# schematic.net
KiCad netlist of a schematic drawn in Altium Designer
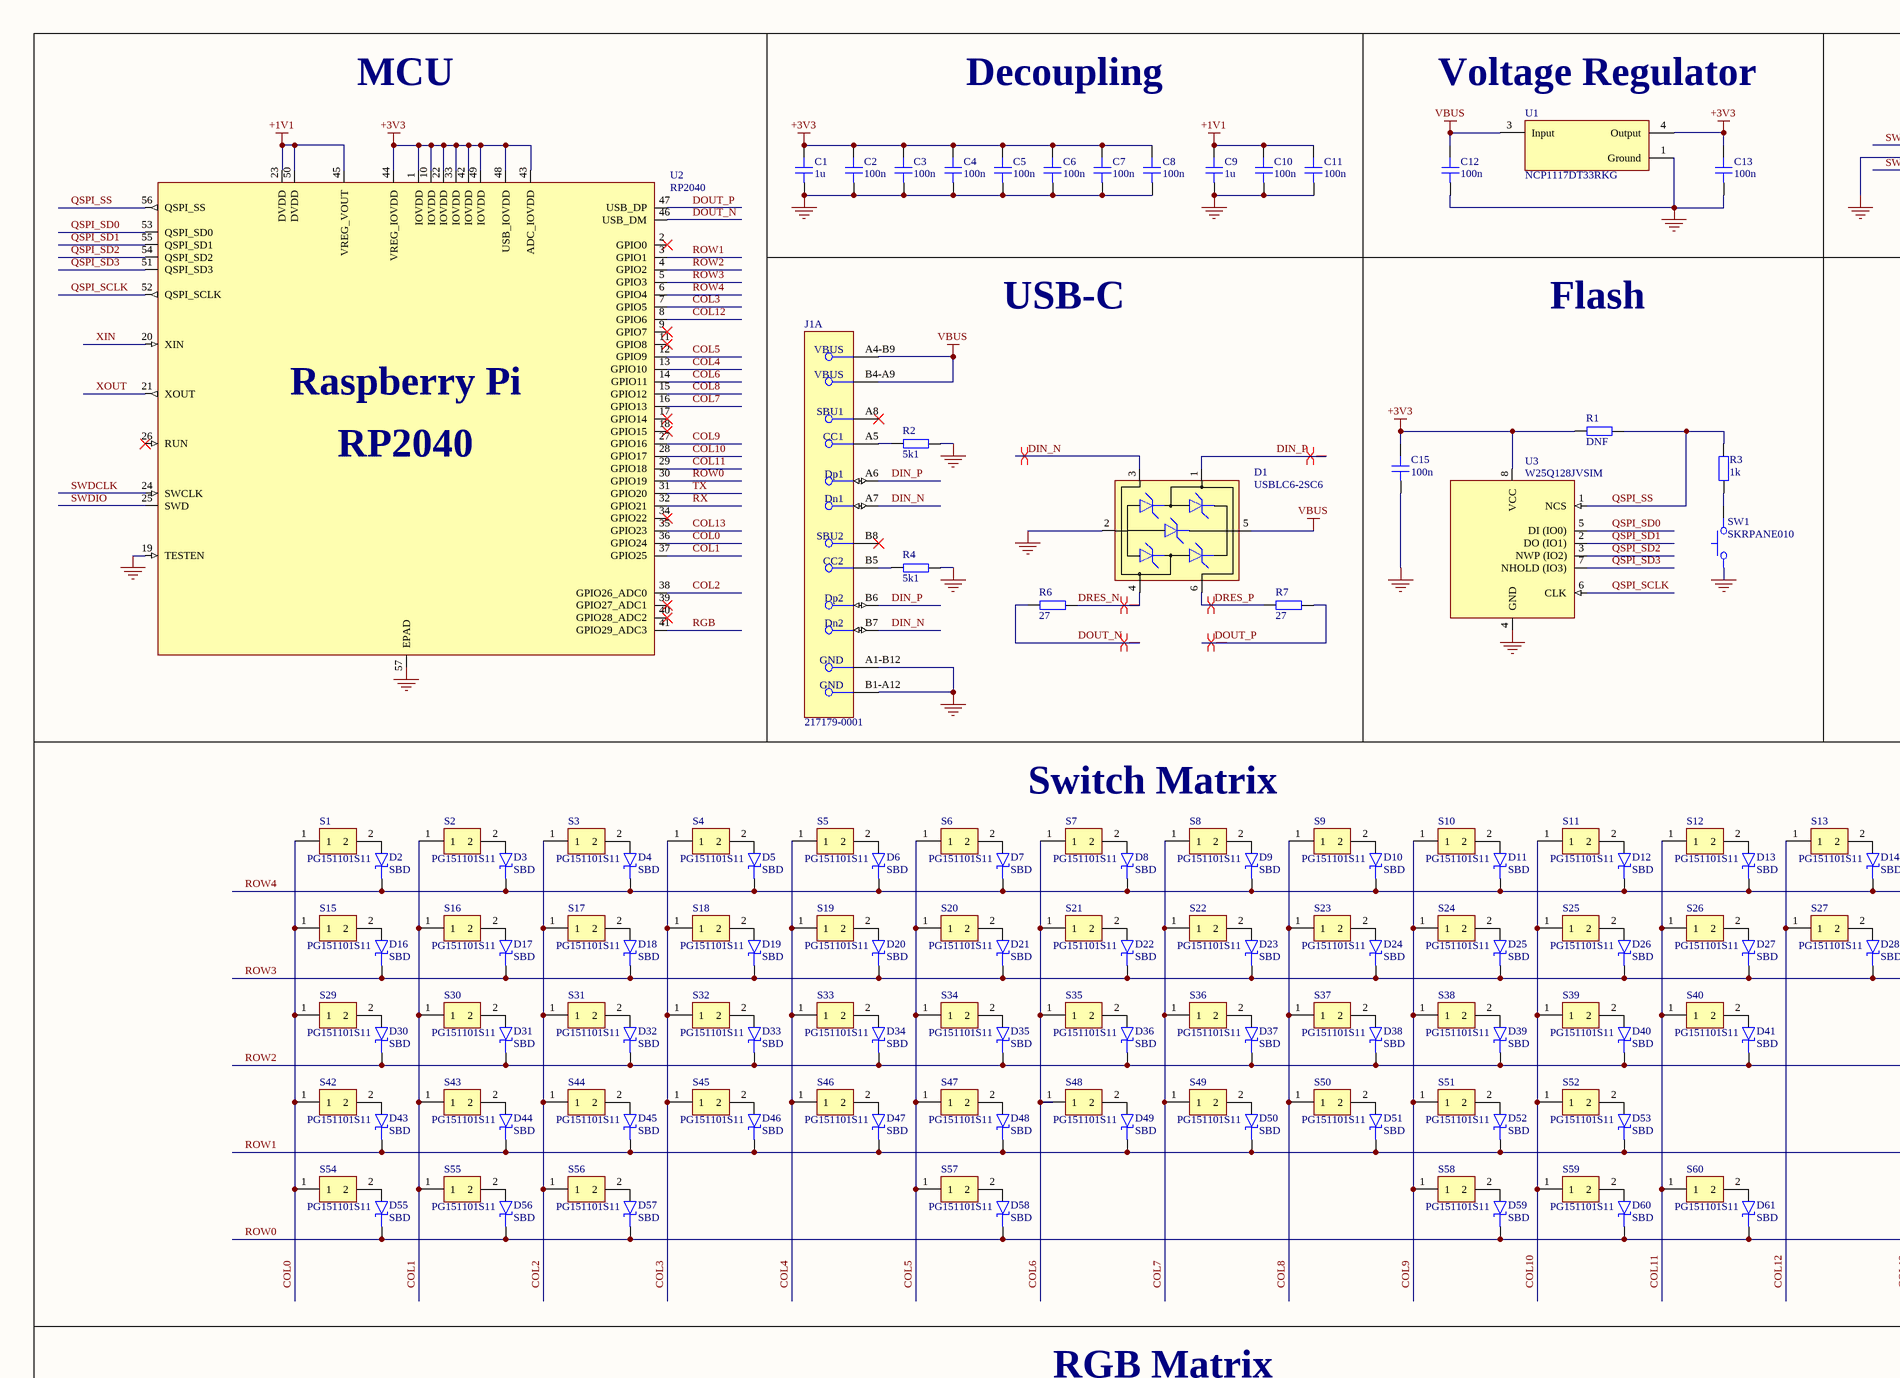
[diagram p0: schematic.SchDoc, top left]
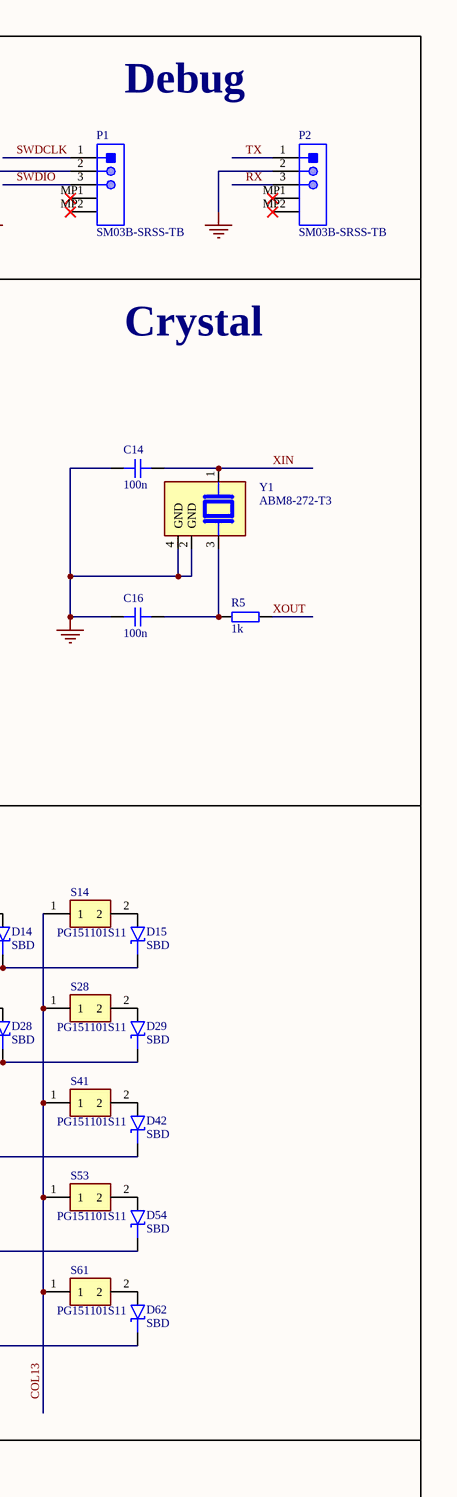
[diagram p1: schematic.SchDoc, top right]
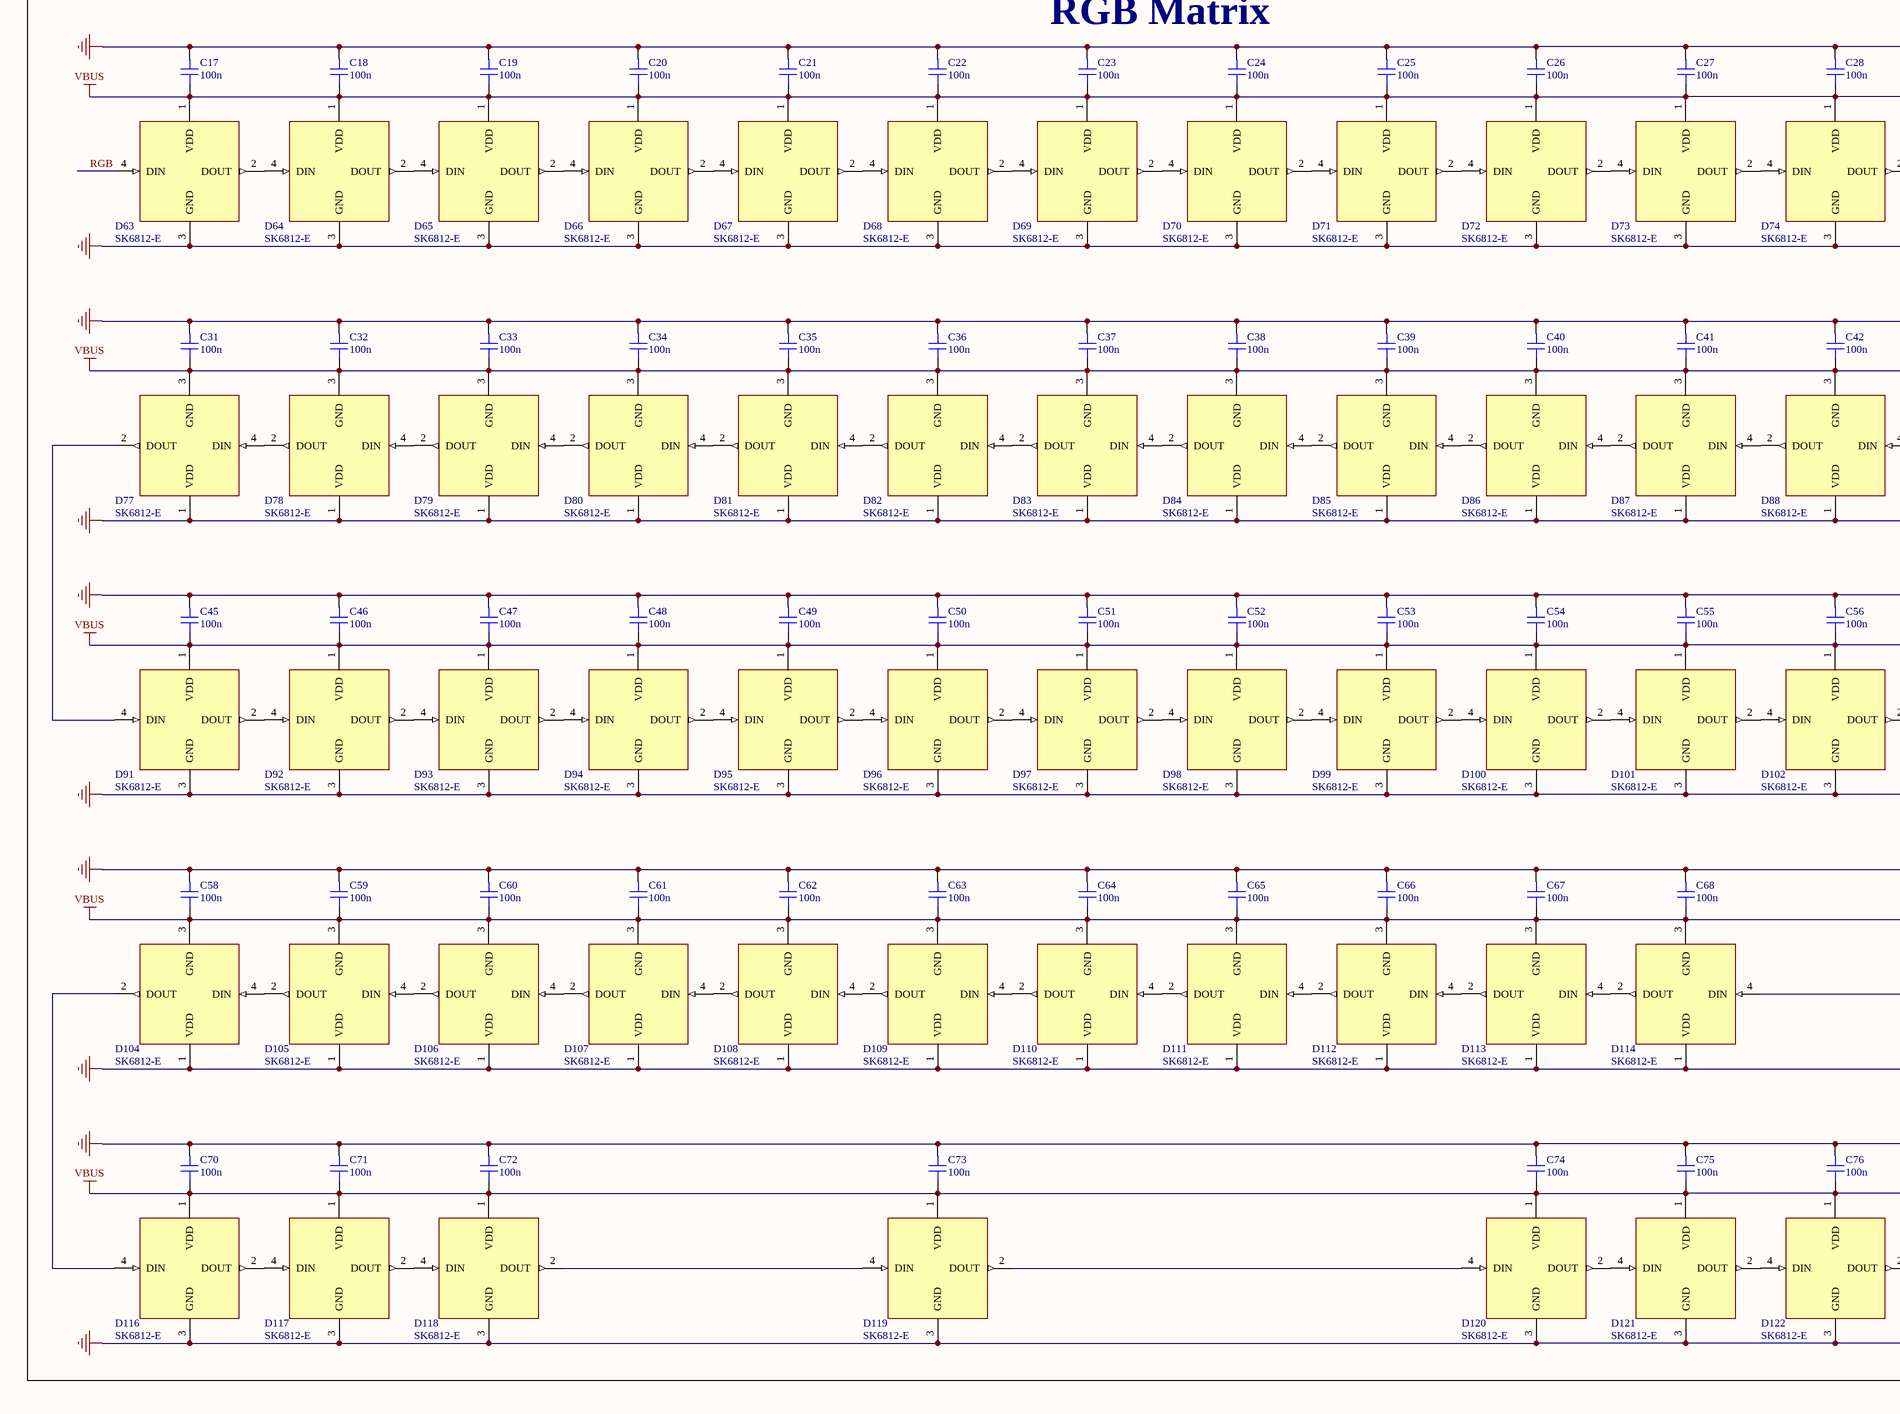
[diagram p2: schematic.SchDoc, bottom left]
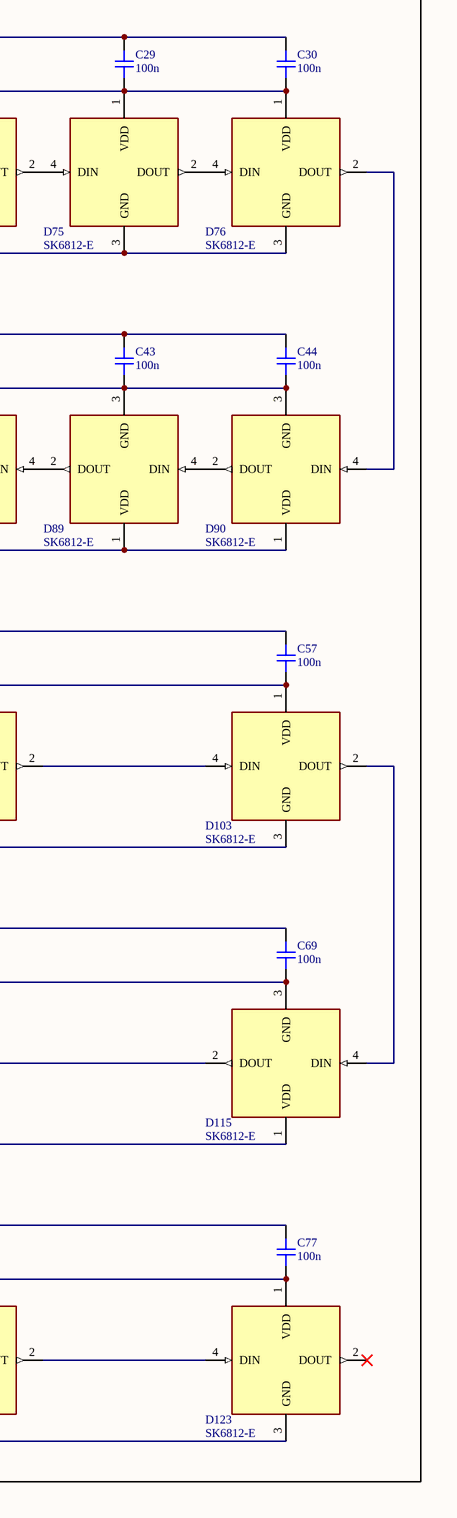
[diagram p3: schematic.SchDoc, bottom right]

(export (version "E")
  (design (tool "Eeschema 10.0.6"))
  (components
    (comp (ref "C1")
      (value "1u")
      (footprint "CAP_0402")
      (description "Capacitor SMD 0402")
      (libsource (lib "Schematic-Lib-PhilsLab") (part "CAP_0402"))
    )
    (comp (ref "C2")
      (value "100n")
      (footprint "CAP_0402")
      (description "Capacitor SMD 0402")
      (libsource (lib "Schematic-Lib-PhilsLab") (part "CAP_0402"))
    )
    (comp (ref "C3")
      (value "100n")
      (footprint "CAP_0402")
      (description "Capacitor SMD 0402")
      (libsource (lib "Schematic-Lib-PhilsLab") (part "CAP_0402"))
    )
    (comp (ref "C4")
      (value "100n")
      (footprint "CAP_0402")
      (description "Capacitor SMD 0402")
      (libsource (lib "Schematic-Lib-PhilsLab") (part "CAP_0402"))
    )
    (comp (ref "C5")
      (value "100n")
      (footprint "CAP_0402")
      (description "Capacitor SMD 0402")
      (libsource (lib "Schematic-Lib-PhilsLab") (part "CAP_0402"))
    )
    (comp (ref "C6")
      (value "100n")
      (footprint "CAP_0402")
      (description "Capacitor SMD 0402")
      (libsource (lib "Schematic-Lib-PhilsLab") (part "CAP_0402"))
    )
    (comp (ref "C7")
      (value "100n")
      (footprint "CAP_0402")
      (description "Capacitor SMD 0402")
      (libsource (lib "Schematic-Lib-PhilsLab") (part "CAP_0402"))
    )
    (comp (ref "C8")
      (value "100n")
      (footprint "CAP_0402")
      (description "Capacitor SMD 0402")
      (libsource (lib "Schematic-Lib-PhilsLab") (part "CAP_0402"))
    )
    (comp (ref "C9")
      (value "1u")
      (footprint "CAP_0402")
      (description "Capacitor SMD 0402")
      (libsource (lib "Schematic-Lib-PhilsLab") (part "CAP_0402"))
    )
    (comp (ref "C10")
      (value "100n")
      (footprint "CAP_0402")
      (description "Capacitor SMD 0402")
      (libsource (lib "Schematic-Lib-PhilsLab") (part "CAP_0402"))
    )
    (comp (ref "C11")
      (value "100n")
      (footprint "CAP_0402")
      (description "Capacitor SMD 0402")
      (libsource (lib "Schematic-Lib-PhilsLab") (part "CAP_0402"))
    )
    (comp (ref "C12")
      (value "100n")
      (footprint "CAP_0402")
      (description "Capacitor SMD 0402")
      (libsource (lib "Schematic-Lib-PhilsLab") (part "CAP_0402"))
    )
    (comp (ref "C13")
      (value "100n")
      (footprint "CAP_0402")
      (description "Capacitor SMD 0402")
      (libsource (lib "Schematic-Lib-PhilsLab") (part "CAP_0402"))
    )
    (comp (ref "C14")
      (value "100n")
      (footprint "CAP_0402")
      (description "Capacitor SMD 0402")
      (libsource (lib "Schematic-Lib-PhilsLab") (part "CAP_0402"))
    )
    (comp (ref "C15")
      (value "100n")
      (footprint "CAP_0402")
      (description "Capacitor SMD 0402")
      (libsource (lib "Schematic-Lib-PhilsLab") (part "CAP_0402"))
    )
    (comp (ref "C16")
      (value "100n")
      (footprint "CAP_0402")
      (description "Capacitor SMD 0402")
      (libsource (lib "Schematic-Lib-PhilsLab") (part "CAP_0402"))
    )
    (comp (ref "C17")
      (value "100n")
      (footprint "CAP_1206")
      (description "Capacitor SMD 1206")
      (libsource (lib "Schematic-Lib-PhilsLab") (part "CAP_1206"))
    )
    (comp (ref "C18")
      (value "100n")
      (footprint "CAP_1206")
      (description "Capacitor SMD 1206")
      (libsource (lib "Schematic-Lib-PhilsLab") (part "CAP_1206"))
    )
    (comp (ref "C19")
      (value "100n")
      (footprint "CAP_1206")
      (description "Capacitor SMD 1206")
      (libsource (lib "Schematic-Lib-PhilsLab") (part "CAP_1206"))
    )
    (comp (ref "C20")
      (value "100n")
      (footprint "CAP_1206")
      (description "Capacitor SMD 1206")
      (libsource (lib "Schematic-Lib-PhilsLab") (part "CAP_1206"))
    )
    (comp (ref "C21")
      (value "100n")
      (footprint "CAP_1206")
      (description "Capacitor SMD 1206")
      (libsource (lib "Schematic-Lib-PhilsLab") (part "CAP_1206"))
    )
    (comp (ref "C22")
      (value "100n")
      (footprint "CAP_1206")
      (description "Capacitor SMD 1206")
      (libsource (lib "Schematic-Lib-PhilsLab") (part "CAP_1206"))
    )
    (comp (ref "C23")
      (value "100n")
      (footprint "CAP_1206")
      (description "Capacitor SMD 1206")
      (libsource (lib "Schematic-Lib-PhilsLab") (part "CAP_1206"))
    )
    (comp (ref "C24")
      (value "100n")
      (footprint "CAP_1206")
      (description "Capacitor SMD 1206")
      (libsource (lib "Schematic-Lib-PhilsLab") (part "CAP_1206"))
    )
    (comp (ref "C25")
      (value "100n")
      (footprint "CAP_1206")
      (description "Capacitor SMD 1206")
      (libsource (lib "Schematic-Lib-PhilsLab") (part "CAP_1206"))
    )
    (comp (ref "C26")
      (value "100n")
      (footprint "CAP_1206")
      (description "Capacitor SMD 1206")
      (libsource (lib "Schematic-Lib-PhilsLab") (part "CAP_1206"))
    )
    (comp (ref "C27")
      (value "100n")
      (footprint "CAP_1206")
      (description "Capacitor SMD 1206")
      (libsource (lib "Schematic-Lib-PhilsLab") (part "CAP_1206"))
    )
    (comp (ref "C28")
      (value "100n")
      (footprint "CAP_1206")
      (description "Capacitor SMD 1206")
      (libsource (lib "Schematic-Lib-PhilsLab") (part "CAP_1206"))
    )
    (comp (ref "C29")
      (value "100n")
      (footprint "CAP_1206")
      (description "Capacitor SMD 1206")
      (libsource (lib "Schematic-Lib-PhilsLab") (part "CAP_1206"))
    )
    (comp (ref "C30")
      (value "100n")
      (footprint "CAP_1206")
      (description "Capacitor SMD 1206")
      (libsource (lib "Schematic-Lib-PhilsLab") (part "CAP_1206"))
    )
    (comp (ref "C31")
      (value "100n")
      (footprint "CAP_1206")
      (description "Capacitor SMD 1206")
      (libsource (lib "Schematic-Lib-PhilsLab") (part "CAP_1206"))
    )
    (comp (ref "C32")
      (value "100n")
      (footprint "CAP_1206")
      (description "Capacitor SMD 1206")
      (libsource (lib "Schematic-Lib-PhilsLab") (part "CAP_1206"))
    )
    (comp (ref "C33")
      (value "100n")
      (footprint "CAP_1206")
      (description "Capacitor SMD 1206")
      (libsource (lib "Schematic-Lib-PhilsLab") (part "CAP_1206"))
    )
    (comp (ref "C34")
      (value "100n")
      (footprint "CAP_1206")
      (description "Capacitor SMD 1206")
      (libsource (lib "Schematic-Lib-PhilsLab") (part "CAP_1206"))
    )
    (comp (ref "C35")
      (value "100n")
      (footprint "CAP_1206")
      (description "Capacitor SMD 1206")
      (libsource (lib "Schematic-Lib-PhilsLab") (part "CAP_1206"))
    )
    (comp (ref "C36")
      (value "100n")
      (footprint "CAP_1206")
      (description "Capacitor SMD 1206")
      (libsource (lib "Schematic-Lib-PhilsLab") (part "CAP_1206"))
    )
    (comp (ref "C37")
      (value "100n")
      (footprint "CAP_1206")
      (description "Capacitor SMD 1206")
      (libsource (lib "Schematic-Lib-PhilsLab") (part "CAP_1206"))
    )
    (comp (ref "C38")
      (value "100n")
      (footprint "CAP_1206")
      (description "Capacitor SMD 1206")
      (libsource (lib "Schematic-Lib-PhilsLab") (part "CAP_1206"))
    )
    (comp (ref "C39")
      (value "100n")
      (footprint "CAP_1206")
      (description "Capacitor SMD 1206")
      (libsource (lib "Schematic-Lib-PhilsLab") (part "CAP_1206"))
    )
    (comp (ref "C40")
      (value "100n")
      (footprint "CAP_1206")
      (description "Capacitor SMD 1206")
      (libsource (lib "Schematic-Lib-PhilsLab") (part "CAP_1206"))
    )
    (comp (ref "C41")
      (value "100n")
      (footprint "CAP_1206")
      (description "Capacitor SMD 1206")
      (libsource (lib "Schematic-Lib-PhilsLab") (part "CAP_1206"))
    )
    (comp (ref "C42")
      (value "100n")
      (footprint "CAP_1206")
      (description "Capacitor SMD 1206")
      (libsource (lib "Schematic-Lib-PhilsLab") (part "CAP_1206"))
    )
    (comp (ref "C43")
      (value "100n")
      (footprint "CAP_1206")
      (description "Capacitor SMD 1206")
      (libsource (lib "Schematic-Lib-PhilsLab") (part "CAP_1206"))
    )
    (comp (ref "C44")
      (value "100n")
      (footprint "CAP_1206")
      (description "Capacitor SMD 1206")
      (libsource (lib "Schematic-Lib-PhilsLab") (part "CAP_1206"))
    )
    (comp (ref "C45")
      (value "100n")
      (footprint "CAP_1206")
      (description "Capacitor SMD 1206")
      (libsource (lib "Schematic-Lib-PhilsLab") (part "CAP_1206"))
    )
    (comp (ref "C46")
      (value "100n")
      (footprint "CAP_1206")
      (description "Capacitor SMD 1206")
      (libsource (lib "Schematic-Lib-PhilsLab") (part "CAP_1206"))
    )
    (comp (ref "C47")
      (value "100n")
      (footprint "CAP_1206")
      (description "Capacitor SMD 1206")
      (libsource (lib "Schematic-Lib-PhilsLab") (part "CAP_1206"))
    )
    (comp (ref "C48")
      (value "100n")
      (footprint "CAP_1206")
      (description "Capacitor SMD 1206")
      (libsource (lib "Schematic-Lib-PhilsLab") (part "CAP_1206"))
    )
    (comp (ref "C49")
      (value "100n")
      (footprint "CAP_1206")
      (description "Capacitor SMD 1206")
      (libsource (lib "Schematic-Lib-PhilsLab") (part "CAP_1206"))
    )
    (comp (ref "C50")
      (value "100n")
      (footprint "CAP_1206")
      (description "Capacitor SMD 1206")
      (libsource (lib "Schematic-Lib-PhilsLab") (part "CAP_1206"))
    )
    (comp (ref "C51")
      (value "100n")
      (footprint "CAP_1206")
      (description "Capacitor SMD 1206")
      (libsource (lib "Schematic-Lib-PhilsLab") (part "CAP_1206"))
    )
    (comp (ref "C52")
      (value "100n")
      (footprint "CAP_1206")
      (description "Capacitor SMD 1206")
      (libsource (lib "Schematic-Lib-PhilsLab") (part "CAP_1206"))
    )
    (comp (ref "C53")
      (value "100n")
      (footprint "CAP_1206")
      (description "Capacitor SMD 1206")
      (libsource (lib "Schematic-Lib-PhilsLab") (part "CAP_1206"))
    )
    (comp (ref "C54")
      (value "100n")
      (footprint "CAP_1206")
      (description "Capacitor SMD 1206")
      (libsource (lib "Schematic-Lib-PhilsLab") (part "CAP_1206"))
    )
    (comp (ref "C55")
      (value "100n")
      (footprint "CAP_1206")
      (description "Capacitor SMD 1206")
      (libsource (lib "Schematic-Lib-PhilsLab") (part "CAP_1206"))
    )
    (comp (ref "C56")
      (value "100n")
      (footprint "CAP_1206")
      (description "Capacitor SMD 1206")
      (libsource (lib "Schematic-Lib-PhilsLab") (part "CAP_1206"))
    )
    (comp (ref "C57")
      (value "100n")
      (footprint "CAP_1206")
      (description "Capacitor SMD 1206")
      (libsource (lib "Schematic-Lib-PhilsLab") (part "CAP_1206"))
    )
    (comp (ref "C58")
      (value "100n")
      (footprint "CAP_1206")
      (description "Capacitor SMD 1206")
      (libsource (lib "Schematic-Lib-PhilsLab") (part "CAP_1206"))
    )
    (comp (ref "C59")
      (value "100n")
      (footprint "CAP_1206")
      (description "Capacitor SMD 1206")
      (libsource (lib "Schematic-Lib-PhilsLab") (part "CAP_1206"))
    )
    (comp (ref "C60")
      (value "100n")
      (footprint "CAP_1206")
      (description "Capacitor SMD 1206")
      (libsource (lib "Schematic-Lib-PhilsLab") (part "CAP_1206"))
    )
    (comp (ref "C61")
      (value "100n")
      (footprint "CAP_1206")
      (description "Capacitor SMD 1206")
      (libsource (lib "Schematic-Lib-PhilsLab") (part "CAP_1206"))
    )
    (comp (ref "C62")
      (value "100n")
      (footprint "CAP_1206")
      (description "Capacitor SMD 1206")
      (libsource (lib "Schematic-Lib-PhilsLab") (part "CAP_1206"))
    )
    (comp (ref "C63")
      (value "100n")
      (footprint "CAP_1206")
      (description "Capacitor SMD 1206")
      (libsource (lib "Schematic-Lib-PhilsLab") (part "CAP_1206"))
    )
    (comp (ref "C64")
      (value "100n")
      (footprint "CAP_1206")
      (description "Capacitor SMD 1206")
      (libsource (lib "Schematic-Lib-PhilsLab") (part "CAP_1206"))
    )
    (comp (ref "C65")
      (value "100n")
      (footprint "CAP_1206")
      (description "Capacitor SMD 1206")
      (libsource (lib "Schematic-Lib-PhilsLab") (part "CAP_1206"))
    )
    (comp (ref "C66")
      (value "100n")
      (footprint "CAP_1206")
      (description "Capacitor SMD 1206")
      (libsource (lib "Schematic-Lib-PhilsLab") (part "CAP_1206"))
    )
    (comp (ref "C67")
      (value "100n")
      (footprint "CAP_1206")
      (description "Capacitor SMD 1206")
      (libsource (lib "Schematic-Lib-PhilsLab") (part "CAP_1206"))
    )
    (comp (ref "C68")
      (value "100n")
      (footprint "CAP_1206")
      (description "Capacitor SMD 1206")
      (libsource (lib "Schematic-Lib-PhilsLab") (part "CAP_1206"))
    )
    (comp (ref "C69")
      (value "100n")
      (footprint "CAP_1206")
      (description "Capacitor SMD 1206")
      (libsource (lib "Schematic-Lib-PhilsLab") (part "CAP_1206"))
    )
    (comp (ref "C70")
      (value "100n")
      (footprint "CAP_1206")
      (description "Capacitor SMD 1206")
      (libsource (lib "Schematic-Lib-PhilsLab") (part "CAP_1206"))
    )
    (comp (ref "C71")
      (value "100n")
      (footprint "CAP_1206")
      (description "Capacitor SMD 1206")
      (libsource (lib "Schematic-Lib-PhilsLab") (part "CAP_1206"))
    )
    (comp (ref "C72")
      (value "100n")
      (footprint "CAP_1206")
      (description "Capacitor SMD 1206")
      (libsource (lib "Schematic-Lib-PhilsLab") (part "CAP_1206"))
    )
    (comp (ref "C73")
      (value "100n")
      (footprint "CAP_1206")
      (description "Capacitor SMD 1206")
      (libsource (lib "Schematic-Lib-PhilsLab") (part "CAP_1206"))
    )
    (comp (ref "C74")
      (value "100n")
      (footprint "CAP_1206")
      (description "Capacitor SMD 1206")
      (libsource (lib "Schematic-Lib-PhilsLab") (part "CAP_1206"))
    )
    (comp (ref "C75")
      (value "100n")
      (footprint "CAP_1206")
      (description "Capacitor SMD 1206")
      (libsource (lib "Schematic-Lib-PhilsLab") (part "CAP_1206"))
    )
    (comp (ref "C76")
      (value "100n")
      (footprint "CAP_1206")
      (description "Capacitor SMD 1206")
      (libsource (lib "Schematic-Lib-PhilsLab") (part "CAP_1206"))
    )
    (comp (ref "C77")
      (value "100n")
      (footprint "CAP_1206")
      (description "Capacitor SMD 1206")
      (libsource (lib "Schematic-Lib-PhilsLab") (part "CAP_1206"))
    )
    (comp (ref "D1")
      (value "USBLC6-2SC6")
      (footprint "SOT-23-6")
      (description "Low-Capacitance ESD Protection USB")
      (fields (field (name "MANUFACTURER") "STMicroelectronics"))
      (libsource (lib "Schematic-Lib-PhilsLab") (part "USBLC6-2SC6"))
    )
    (comp (ref "D2")
      (value "SBD")
      (footprint "SOD-323")
      (description "Diode Schottky SMD SOD-323")
      (libsource (lib "Schematic-Lib-PhilsLab") (part "D_SCHOTTKY_SOD_323"))
    )
    (comp (ref "D3")
      (value "SBD")
      (footprint "SOD-323")
      (description "Diode Schottky SMD SOD-323")
      (libsource (lib "Schematic-Lib-PhilsLab") (part "D_SCHOTTKY_SOD_323"))
    )
    (comp (ref "D4")
      (value "SBD")
      (footprint "SOD-323")
      (description "Diode Schottky SMD SOD-323")
      (libsource (lib "Schematic-Lib-PhilsLab") (part "D_SCHOTTKY_SOD_323"))
    )
    (comp (ref "D5")
      (value "SBD")
      (footprint "SOD-323")
      (description "Diode Schottky SMD SOD-323")
      (libsource (lib "Schematic-Lib-PhilsLab") (part "D_SCHOTTKY_SOD_323"))
    )
    (comp (ref "D6")
      (value "SBD")
      (footprint "SOD-323")
      (description "Diode Schottky SMD SOD-323")
      (libsource (lib "Schematic-Lib-PhilsLab") (part "D_SCHOTTKY_SOD_323"))
    )
    (comp (ref "D7")
      (value "SBD")
      (footprint "SOD-323")
      (description "Diode Schottky SMD SOD-323")
      (libsource (lib "Schematic-Lib-PhilsLab") (part "D_SCHOTTKY_SOD_323"))
    )
    (comp (ref "D8")
      (value "SBD")
      (footprint "SOD-323")
      (description "Diode Schottky SMD SOD-323")
      (libsource (lib "Schematic-Lib-PhilsLab") (part "D_SCHOTTKY_SOD_323"))
    )
    (comp (ref "D9")
      (value "SBD")
      (footprint "SOD-323")
      (description "Diode Schottky SMD SOD-323")
      (libsource (lib "Schematic-Lib-PhilsLab") (part "D_SCHOTTKY_SOD_323"))
    )
    (comp (ref "D10")
      (value "SBD")
      (footprint "SOD-323")
      (description "Diode Schottky SMD SOD-323")
      (libsource (lib "Schematic-Lib-PhilsLab") (part "D_SCHOTTKY_SOD_323"))
    )
    (comp (ref "D11")
      (value "SBD")
      (footprint "SOD-323")
      (description "Diode Schottky SMD SOD-323")
      (libsource (lib "Schematic-Lib-PhilsLab") (part "D_SCHOTTKY_SOD_323"))
    )
    (comp (ref "D12")
      (value "SBD")
      (footprint "SOD-323")
      (description "Diode Schottky SMD SOD-323")
      (libsource (lib "Schematic-Lib-PhilsLab") (part "D_SCHOTTKY_SOD_323"))
    )
    (comp (ref "D13")
      (value "SBD")
      (footprint "SOD-323")
      (description "Diode Schottky SMD SOD-323")
      (libsource (lib "Schematic-Lib-PhilsLab") (part "D_SCHOTTKY_SOD_323"))
    )
    (comp (ref "D14")
      (value "SBD")
      (footprint "SOD-323")
      (description "Diode Schottky SMD SOD-323")
      (libsource (lib "Schematic-Lib-PhilsLab") (part "D_SCHOTTKY_SOD_323"))
    )
    (comp (ref "D15")
      (value "SBD")
      (footprint "SOD-323")
      (description "Diode Schottky SMD SOD-323")
      (libsource (lib "Schematic-Lib-PhilsLab") (part "D_SCHOTTKY_SOD_323"))
    )
    (comp (ref "D16")
      (value "SBD")
      (footprint "SOD-323")
      (description "Diode Schottky SMD SOD-323")
      (libsource (lib "Schematic-Lib-PhilsLab") (part "D_SCHOTTKY_SOD_323"))
    )
    (comp (ref "D17")
      (value "SBD")
      (footprint "SOD-323")
      (description "Diode Schottky SMD SOD-323")
      (libsource (lib "Schematic-Lib-PhilsLab") (part "D_SCHOTTKY_SOD_323"))
    )
    (comp (ref "D18")
      (value "SBD")
      (footprint "SOD-323")
      (description "Diode Schottky SMD SOD-323")
      (libsource (lib "Schematic-Lib-PhilsLab") (part "D_SCHOTTKY_SOD_323"))
    )
    (comp (ref "D19")
      (value "SBD")
      (footprint "SOD-323")
      (description "Diode Schottky SMD SOD-323")
      (libsource (lib "Schematic-Lib-PhilsLab") (part "D_SCHOTTKY_SOD_323"))
    )
    (comp (ref "D20")
      (value "SBD")
      (footprint "SOD-323")
      (description "Diode Schottky SMD SOD-323")
      (libsource (lib "Schematic-Lib-PhilsLab") (part "D_SCHOTTKY_SOD_323"))
    )
    (comp (ref "D21")
      (value "SBD")
      (footprint "SOD-323")
      (description "Diode Schottky SMD SOD-323")
      (libsource (lib "Schematic-Lib-PhilsLab") (part "D_SCHOTTKY_SOD_323"))
    )
    (comp (ref "D22")
      (value "SBD")
      (footprint "SOD-323")
      (description "Diode Schottky SMD SOD-323")
      (libsource (lib "Schematic-Lib-PhilsLab") (part "D_SCHOTTKY_SOD_323"))
    )
    (comp (ref "D23")
      (value "SBD")
      (footprint "SOD-323")
      (description "Diode Schottky SMD SOD-323")
      (libsource (lib "Schematic-Lib-PhilsLab") (part "D_SCHOTTKY_SOD_323"))
    )
    (comp (ref "D24")
      (value "SBD")
      (footprint "SOD-323")
      (description "Diode Schottky SMD SOD-323")
      (libsource (lib "Schematic-Lib-PhilsLab") (part "D_SCHOTTKY_SOD_323"))
    )
    (comp (ref "D25")
      (value "SBD")
      (footprint "SOD-323")
      (description "Diode Schottky SMD SOD-323")
      (libsource (lib "Schematic-Lib-PhilsLab") (part "D_SCHOTTKY_SOD_323"))
    )
    (comp (ref "D26")
      (value "SBD")
      (footprint "SOD-323")
      (description "Diode Schottky SMD SOD-323")
      (libsource (lib "Schematic-Lib-PhilsLab") (part "D_SCHOTTKY_SOD_323"))
    )
    (comp (ref "D27")
      (value "SBD")
      (footprint "SOD-323")
      (description "Diode Schottky SMD SOD-323")
      (libsource (lib "Schematic-Lib-PhilsLab") (part "D_SCHOTTKY_SOD_323"))
    )
    (comp (ref "D28")
      (value "SBD")
      (footprint "SOD-323")
      (description "Diode Schottky SMD SOD-323")
      (libsource (lib "Schematic-Lib-PhilsLab") (part "D_SCHOTTKY_SOD_323"))
    )
    (comp (ref "D29")
      (value "SBD")
      (footprint "SOD-323")
      (description "Diode Schottky SMD SOD-323")
      (libsource (lib "Schematic-Lib-PhilsLab") (part "D_SCHOTTKY_SOD_323"))
    )
    (comp (ref "D30")
      (value "SBD")
      (footprint "SOD-323")
      (description "Diode Schottky SMD SOD-323")
      (libsource (lib "Schematic-Lib-PhilsLab") (part "D_SCHOTTKY_SOD_323"))
    )
    (comp (ref "D31")
      (value "SBD")
      (footprint "SOD-323")
      (description "Diode Schottky SMD SOD-323")
      (libsource (lib "Schematic-Lib-PhilsLab") (part "D_SCHOTTKY_SOD_323"))
    )
    (comp (ref "D32")
      (value "SBD")
      (footprint "SOD-323")
      (description "Diode Schottky SMD SOD-323")
      (libsource (lib "Schematic-Lib-PhilsLab") (part "D_SCHOTTKY_SOD_323"))
    )
    (comp (ref "D33")
      (value "SBD")
      (footprint "SOD-323")
      (description "Diode Schottky SMD SOD-323")
      (libsource (lib "Schematic-Lib-PhilsLab") (part "D_SCHOTTKY_SOD_323"))
    )
    (comp (ref "D34")
      (value "SBD")
      (footprint "SOD-323")
      (description "Diode Schottky SMD SOD-323")
      (libsource (lib "Schematic-Lib-PhilsLab") (part "D_SCHOTTKY_SOD_323"))
    )
    (comp (ref "D35")
      (value "SBD")
      (footprint "SOD-323")
      (description "Diode Schottky SMD SOD-323")
      (libsource (lib "Schematic-Lib-PhilsLab") (part "D_SCHOTTKY_SOD_323"))
    )
    (comp (ref "D36")
      (value "SBD")
      (footprint "SOD-323")
      (description "Diode Schottky SMD SOD-323")
      (libsource (lib "Schematic-Lib-PhilsLab") (part "D_SCHOTTKY_SOD_323"))
    )
    (comp (ref "D37")
      (value "SBD")
      (footprint "SOD-323")
      (description "Diode Schottky SMD SOD-323")
      (libsource (lib "Schematic-Lib-PhilsLab") (part "D_SCHOTTKY_SOD_323"))
    )
    (comp (ref "D38")
      (value "SBD")
      (footprint "SOD-323")
      (description "Diode Schottky SMD SOD-323")
      (libsource (lib "Schematic-Lib-PhilsLab") (part "D_SCHOTTKY_SOD_323"))
    )
    (comp (ref "D39")
      (value "SBD")
      (footprint "SOD-323")
      (description "Diode Schottky SMD SOD-323")
      (libsource (lib "Schematic-Lib-PhilsLab") (part "D_SCHOTTKY_SOD_323"))
    )
    (comp (ref "D40")
      (value "SBD")
      (footprint "SOD-323")
      (description "Diode Schottky SMD SOD-323")
      (libsource (lib "Schematic-Lib-PhilsLab") (part "D_SCHOTTKY_SOD_323"))
    )
    (comp (ref "D41")
      (value "SBD")
      (footprint "SOD-323")
      (description "Diode Schottky SMD SOD-323")
      (libsource (lib "Schematic-Lib-PhilsLab") (part "D_SCHOTTKY_SOD_323"))
    )
    (comp (ref "D42")
      (value "SBD")
      (footprint "SOD-323")
      (description "Diode Schottky SMD SOD-323")
      (libsource (lib "Schematic-Lib-PhilsLab") (part "D_SCHOTTKY_SOD_323"))
    )
    (comp (ref "D43")
      (value "SBD")
      (footprint "SOD-323")
      (description "Diode Schottky SMD SOD-323")
      (libsource (lib "Schematic-Lib-PhilsLab") (part "D_SCHOTTKY_SOD_323"))
    )
    (comp (ref "D44")
      (value "SBD")
      (footprint "SOD-323")
      (description "Diode Schottky SMD SOD-323")
      (libsource (lib "Schematic-Lib-PhilsLab") (part "D_SCHOTTKY_SOD_323"))
    )
    (comp (ref "D45")
      (value "SBD")
      (footprint "SOD-323")
      (description "Diode Schottky SMD SOD-323")
      (libsource (lib "Schematic-Lib-PhilsLab") (part "D_SCHOTTKY_SOD_323"))
    )
    (comp (ref "D46")
      (value "SBD")
      (footprint "SOD-323")
      (description "Diode Schottky SMD SOD-323")
      (libsource (lib "Schematic-Lib-PhilsLab") (part "D_SCHOTTKY_SOD_323"))
    )
    (comp (ref "D47")
      (value "SBD")
      (footprint "SOD-323")
      (description "Diode Schottky SMD SOD-323")
      (libsource (lib "Schematic-Lib-PhilsLab") (part "D_SCHOTTKY_SOD_323"))
    )
    (comp (ref "D48")
      (value "SBD")
      (footprint "SOD-323")
      (description "Diode Schottky SMD SOD-323")
      (libsource (lib "Schematic-Lib-PhilsLab") (part "D_SCHOTTKY_SOD_323"))
    )
    (comp (ref "D49")
      (value "SBD")
      (footprint "SOD-323")
      (description "Diode Schottky SMD SOD-323")
      (libsource (lib "Schematic-Lib-PhilsLab") (part "D_SCHOTTKY_SOD_323"))
    )
    (comp (ref "D50")
      (value "SBD")
      (footprint "SOD-323")
      (description "Diode Schottky SMD SOD-323")
      (libsource (lib "Schematic-Lib-PhilsLab") (part "D_SCHOTTKY_SOD_323"))
    )
    (comp (ref "D51")
      (value "SBD")
      (footprint "SOD-323")
      (description "Diode Schottky SMD SOD-323")
      (libsource (lib "Schematic-Lib-PhilsLab") (part "D_SCHOTTKY_SOD_323"))
    )
    (comp (ref "D52")
      (value "SBD")
      (footprint "SOD-323")
      (description "Diode Schottky SMD SOD-323")
      (libsource (lib "Schematic-Lib-PhilsLab") (part "D_SCHOTTKY_SOD_323"))
    )
    (comp (ref "D53")
      (value "SBD")
      (footprint "SOD-323")
      (description "Diode Schottky SMD SOD-323")
      (libsource (lib "Schematic-Lib-PhilsLab") (part "D_SCHOTTKY_SOD_323"))
    )
    (comp (ref "D54")
      (value "SBD")
      (footprint "SOD-323")
      (description "Diode Schottky SMD SOD-323")
      (libsource (lib "Schematic-Lib-PhilsLab") (part "D_SCHOTTKY_SOD_323"))
    )
    (comp (ref "D55")
      (value "SBD")
      (footprint "SOD-323")
      (description "Diode Schottky SMD SOD-323")
      (libsource (lib "Schematic-Lib-PhilsLab") (part "D_SCHOTTKY_SOD_323"))
    )
    (comp (ref "D56")
      (value "SBD")
      (footprint "SOD-323")
      (description "Diode Schottky SMD SOD-323")
      (libsource (lib "Schematic-Lib-PhilsLab") (part "D_SCHOTTKY_SOD_323"))
    )
    (comp (ref "D57")
      (value "SBD")
      (footprint "SOD-323")
      (description "Diode Schottky SMD SOD-323")
      (libsource (lib "Schematic-Lib-PhilsLab") (part "D_SCHOTTKY_SOD_323"))
    )
    (comp (ref "D58")
      (value "SBD")
      (footprint "SOD-323")
      (description "Diode Schottky SMD SOD-323")
      (libsource (lib "Schematic-Lib-PhilsLab") (part "D_SCHOTTKY_SOD_323"))
    )
    (comp (ref "D59")
      (value "SBD")
      (footprint "SOD-323")
      (description "Diode Schottky SMD SOD-323")
      (libsource (lib "Schematic-Lib-PhilsLab") (part "D_SCHOTTKY_SOD_323"))
    )
    (comp (ref "D60")
      (value "SBD")
      (footprint "SOD-323")
      (description "Diode Schottky SMD SOD-323")
      (libsource (lib "Schematic-Lib-PhilsLab") (part "D_SCHOTTKY_SOD_323"))
    )
    (comp (ref "D61")
      (value "SBD")
      (footprint "SOD-323")
      (description "Diode Schottky SMD SOD-323")
      (libsource (lib "Schematic-Lib-PhilsLab") (part "D_SCHOTTKY_SOD_323"))
    )
    (comp (ref "D62")
      (value "SBD")
      (footprint "SOD-323")
      (description "Diode Schottky SMD SOD-323")
      (libsource (lib "Schematic-Lib-PhilsLab") (part "D_SCHOTTKY_SOD_323"))
    )
    (comp (ref "D63")
      (value "SK6812-E")
      (footprint "LED_SK6812-E")
      (fields (field (name "MF") "DONGGUANG OPSCO OPTOELECTRONICS CO., LTD"))
      (libsource (lib "Schematic-Lib-PhilsLab") (part "SK6812-E"))
    )
    (comp (ref "D64")
      (value "SK6812-E")
      (footprint "LED_SK6812-E")
      (fields (field (name "MF") "DONGGUANG OPSCO OPTOELECTRONICS CO., LTD"))
      (libsource (lib "Schematic-Lib-PhilsLab") (part "SK6812-E"))
    )
    (comp (ref "D65")
      (value "SK6812-E")
      (footprint "LED_SK6812-E")
      (fields (field (name "MF") "DONGGUANG OPSCO OPTOELECTRONICS CO., LTD"))
      (libsource (lib "Schematic-Lib-PhilsLab") (part "SK6812-E"))
    )
    (comp (ref "D66")
      (value "SK6812-E")
      (footprint "LED_SK6812-E")
      (fields (field (name "MF") "DONGGUANG OPSCO OPTOELECTRONICS CO., LTD"))
      (libsource (lib "Schematic-Lib-PhilsLab") (part "SK6812-E"))
    )
    (comp (ref "D67")
      (value "SK6812-E")
      (footprint "LED_SK6812-E")
      (fields (field (name "MF") "DONGGUANG OPSCO OPTOELECTRONICS CO., LTD"))
      (libsource (lib "Schematic-Lib-PhilsLab") (part "SK6812-E"))
    )
    (comp (ref "D68")
      (value "SK6812-E")
      (footprint "LED_SK6812-E")
      (fields (field (name "MF") "DONGGUANG OPSCO OPTOELECTRONICS CO., LTD"))
      (libsource (lib "Schematic-Lib-PhilsLab") (part "SK6812-E"))
    )
    (comp (ref "D69")
      (value "SK6812-E")
      (footprint "LED_SK6812-E")
      (fields (field (name "MF") "DONGGUANG OPSCO OPTOELECTRONICS CO., LTD"))
      (libsource (lib "Schematic-Lib-PhilsLab") (part "SK6812-E"))
    )
    (comp (ref "D70")
      (value "SK6812-E")
      (footprint "LED_SK6812-E")
      (fields (field (name "MF") "DONGGUANG OPSCO OPTOELECTRONICS CO., LTD"))
      (libsource (lib "Schematic-Lib-PhilsLab") (part "SK6812-E"))
    )
    (comp (ref "D71")
      (value "SK6812-E")
      (footprint "LED_SK6812-E")
      (fields (field (name "MF") "DONGGUANG OPSCO OPTOELECTRONICS CO., LTD"))
      (libsource (lib "Schematic-Lib-PhilsLab") (part "SK6812-E"))
    )
    (comp (ref "D72")
      (value "SK6812-E")
      (footprint "LED_SK6812-E")
      (fields (field (name "MF") "DONGGUANG OPSCO OPTOELECTRONICS CO., LTD"))
      (libsource (lib "Schematic-Lib-PhilsLab") (part "SK6812-E"))
    )
    (comp (ref "D73")
      (value "SK6812-E")
      (footprint "LED_SK6812-E")
      (fields (field (name "MF") "DONGGUANG OPSCO OPTOELECTRONICS CO., LTD"))
      (libsource (lib "Schematic-Lib-PhilsLab") (part "SK6812-E"))
    )
    (comp (ref "D74")
      (value "SK6812-E")
      (footprint "LED_SK6812-E")
      (fields (field (name "MF") "DONGGUANG OPSCO OPTOELECTRONICS CO., LTD"))
      (libsource (lib "Schematic-Lib-PhilsLab") (part "SK6812-E"))
    )
    (comp (ref "D75")
      (value "SK6812-E")
      (footprint "LED_SK6812-E")
      (fields (field (name "MF") "DONGGUANG OPSCO OPTOELECTRONICS CO., LTD"))
      (libsource (lib "Schematic-Lib-PhilsLab") (part "SK6812-E"))
    )
    (comp (ref "D76")
      (value "SK6812-E")
      (footprint "LED_SK6812-E")
      (fields (field (name "MF") "DONGGUANG OPSCO OPTOELECTRONICS CO., LTD"))
      (libsource (lib "Schematic-Lib-PhilsLab") (part "SK6812-E"))
    )
    (comp (ref "D77")
      (value "SK6812-E")
      (footprint "LED_SK6812-E")
      (fields (field (name "MF") "DONGGUANG OPSCO OPTOELECTRONICS CO., LTD"))
      (libsource (lib "") (part "SK6812-E_1"))
    )
    (comp (ref "D78")
      (value "SK6812-E")
      (footprint "LED_SK6812-E")
      (fields (field (name "MF") "DONGGUANG OPSCO OPTOELECTRONICS CO., LTD"))
      (libsource (lib "") (part "SK6812-E_1"))
    )
    (comp (ref "D79")
      (value "SK6812-E")
      (footprint "LED_SK6812-E")
      (fields (field (name "MF") "DONGGUANG OPSCO OPTOELECTRONICS CO., LTD"))
      (libsource (lib "") (part "SK6812-E_1"))
    )
    (comp (ref "D80")
      (value "SK6812-E")
      (footprint "LED_SK6812-E")
      (fields (field (name "MF") "DONGGUANG OPSCO OPTOELECTRONICS CO., LTD"))
      (libsource (lib "") (part "SK6812-E_1"))
    )
    (comp (ref "D81")
      (value "SK6812-E")
      (footprint "LED_SK6812-E")
      (fields (field (name "MF") "DONGGUANG OPSCO OPTOELECTRONICS CO., LTD"))
      (libsource (lib "") (part "SK6812-E_1"))
    )
    (comp (ref "D82")
      (value "SK6812-E")
      (footprint "LED_SK6812-E")
      (fields (field (name "MF") "DONGGUANG OPSCO OPTOELECTRONICS CO., LTD"))
      (libsource (lib "") (part "SK6812-E_1"))
    )
    (comp (ref "D83")
      (value "SK6812-E")
      (footprint "LED_SK6812-E")
      (fields (field (name "MF") "DONGGUANG OPSCO OPTOELECTRONICS CO., LTD"))
      (libsource (lib "") (part "SK6812-E_1"))
    )
    (comp (ref "D84")
      (value "SK6812-E")
      (footprint "LED_SK6812-E")
      (fields (field (name "MF") "DONGGUANG OPSCO OPTOELECTRONICS CO., LTD"))
      (libsource (lib "") (part "SK6812-E_1"))
    )
    (comp (ref "D85")
      (value "SK6812-E")
      (footprint "LED_SK6812-E")
      (fields (field (name "MF") "DONGGUANG OPSCO OPTOELECTRONICS CO., LTD"))
      (libsource (lib "") (part "SK6812-E_1"))
    )
    (comp (ref "D86")
      (value "SK6812-E")
      (footprint "LED_SK6812-E")
      (fields (field (name "MF") "DONGGUANG OPSCO OPTOELECTRONICS CO., LTD"))
      (libsource (lib "") (part "SK6812-E_1"))
    )
    (comp (ref "D87")
      (value "SK6812-E")
      (footprint "LED_SK6812-E")
      (fields (field (name "MF") "DONGGUANG OPSCO OPTOELECTRONICS CO., LTD"))
      (libsource (lib "") (part "SK6812-E_1"))
    )
    (comp (ref "D88")
      (value "SK6812-E")
      (footprint "LED_SK6812-E")
      (fields (field (name "MF") "DONGGUANG OPSCO OPTOELECTRONICS CO., LTD"))
      (libsource (lib "") (part "SK6812-E_1"))
    )
    (comp (ref "D89")
      (value "SK6812-E")
      (footprint "LED_SK6812-E")
      (fields (field (name "MF") "DONGGUANG OPSCO OPTOELECTRONICS CO., LTD"))
      (libsource (lib "") (part "SK6812-E_1"))
    )
    (comp (ref "D90")
      (value "SK6812-E")
      (footprint "LED_SK6812-E")
      (fields (field (name "MF") "DONGGUANG OPSCO OPTOELECTRONICS CO., LTD"))
      (libsource (lib "") (part "SK6812-E_1"))
    )
    (comp (ref "D91")
      (value "SK6812-E")
      (footprint "LED_SK6812-E")
      (fields (field (name "MF") "DONGGUANG OPSCO OPTOELECTRONICS CO., LTD"))
      (libsource (lib "Schematic-Lib-PhilsLab") (part "SK6812-E"))
    )
    (comp (ref "D92")
      (value "SK6812-E")
      (footprint "LED_SK6812-E")
      (fields (field (name "MF") "DONGGUANG OPSCO OPTOELECTRONICS CO., LTD"))
      (libsource (lib "Schematic-Lib-PhilsLab") (part "SK6812-E"))
    )
    (comp (ref "D93")
      (value "SK6812-E")
      (footprint "LED_SK6812-E")
      (fields (field (name "MF") "DONGGUANG OPSCO OPTOELECTRONICS CO., LTD"))
      (libsource (lib "Schematic-Lib-PhilsLab") (part "SK6812-E"))
    )
    (comp (ref "D94")
      (value "SK6812-E")
      (footprint "LED_SK6812-E")
      (fields (field (name "MF") "DONGGUANG OPSCO OPTOELECTRONICS CO., LTD"))
      (libsource (lib "Schematic-Lib-PhilsLab") (part "SK6812-E"))
    )
    (comp (ref "D95")
      (value "SK6812-E")
      (footprint "LED_SK6812-E")
      (fields (field (name "MF") "DONGGUANG OPSCO OPTOELECTRONICS CO., LTD"))
      (libsource (lib "Schematic-Lib-PhilsLab") (part "SK6812-E"))
    )
    (comp (ref "D96")
      (value "SK6812-E")
      (footprint "LED_SK6812-E")
      (fields (field (name "MF") "DONGGUANG OPSCO OPTOELECTRONICS CO., LTD"))
      (libsource (lib "Schematic-Lib-PhilsLab") (part "SK6812-E"))
    )
    (comp (ref "D97")
      (value "SK6812-E")
      (footprint "LED_SK6812-E")
      (fields (field (name "MF") "DONGGUANG OPSCO OPTOELECTRONICS CO., LTD"))
      (libsource (lib "Schematic-Lib-PhilsLab") (part "SK6812-E"))
    )
    (comp (ref "D98")
      (value "SK6812-E")
      (footprint "LED_SK6812-E")
      (fields (field (name "MF") "DONGGUANG OPSCO OPTOELECTRONICS CO., LTD"))
      (libsource (lib "Schematic-Lib-PhilsLab") (part "SK6812-E"))
    )
    (comp (ref "D99")
      (value "SK6812-E")
      (footprint "LED_SK6812-E")
      (fields (field (name "MF") "DONGGUANG OPSCO OPTOELECTRONICS CO., LTD"))
      (libsource (lib "Schematic-Lib-PhilsLab") (part "SK6812-E"))
    )
    (comp (ref "D100")
      (value "SK6812-E")
      (footprint "LED_SK6812-E")
      (fields (field (name "MF") "DONGGUANG OPSCO OPTOELECTRONICS CO., LTD"))
      (libsource (lib "Schematic-Lib-PhilsLab") (part "SK6812-E"))
    )
    (comp (ref "D101")
      (value "SK6812-E")
      (footprint "LED_SK6812-E")
      (fields (field (name "MF") "DONGGUANG OPSCO OPTOELECTRONICS CO., LTD"))
      (libsource (lib "Schematic-Lib-PhilsLab") (part "SK6812-E"))
    )
    (comp (ref "D102")
      (value "SK6812-E")
      (footprint "LED_SK6812-E")
      (fields (field (name "MF") "DONGGUANG OPSCO OPTOELECTRONICS CO., LTD"))
      (libsource (lib "Schematic-Lib-PhilsLab") (part "SK6812-E"))
    )
    (comp (ref "D103")
      (value "SK6812-E")
      (footprint "LED_SK6812-E")
      (fields (field (name "MF") "DONGGUANG OPSCO OPTOELECTRONICS CO., LTD"))
      (libsource (lib "Schematic-Lib-PhilsLab") (part "SK6812-E"))
    )
    (comp (ref "D104")
      (value "SK6812-E")
      (footprint "LED_SK6812-E")
      (fields (field (name "MF") "DONGGUANG OPSCO OPTOELECTRONICS CO., LTD"))
      (libsource (lib "") (part "SK6812-E_1"))
    )
    (comp (ref "D105")
      (value "SK6812-E")
      (footprint "LED_SK6812-E")
      (fields (field (name "MF") "DONGGUANG OPSCO OPTOELECTRONICS CO., LTD"))
      (libsource (lib "") (part "SK6812-E_1"))
    )
    (comp (ref "D106")
      (value "SK6812-E")
      (footprint "LED_SK6812-E")
      (fields (field (name "MF") "DONGGUANG OPSCO OPTOELECTRONICS CO., LTD"))
      (libsource (lib "") (part "SK6812-E_1"))
    )
    (comp (ref "D107")
      (value "SK6812-E")
      (footprint "LED_SK6812-E")
      (fields (field (name "MF") "DONGGUANG OPSCO OPTOELECTRONICS CO., LTD"))
      (libsource (lib "") (part "SK6812-E_1"))
    )
    (comp (ref "D108")
      (value "SK6812-E")
      (footprint "LED_SK6812-E")
      (fields (field (name "MF") "DONGGUANG OPSCO OPTOELECTRONICS CO., LTD"))
      (libsource (lib "") (part "SK6812-E_1"))
    )
    (comp (ref "D109")
      (value "SK6812-E")
      (footprint "LED_SK6812-E")
      (fields (field (name "MF") "DONGGUANG OPSCO OPTOELECTRONICS CO., LTD"))
      (libsource (lib "") (part "SK6812-E_1"))
    )
    (comp (ref "D110")
      (value "SK6812-E")
      (footprint "LED_SK6812-E")
      (fields (field (name "MF") "DONGGUANG OPSCO OPTOELECTRONICS CO., LTD"))
      (libsource (lib "") (part "SK6812-E_1"))
    )
    (comp (ref "D111")
      (value "SK6812-E")
      (footprint "LED_SK6812-E")
      (fields (field (name "MF") "DONGGUANG OPSCO OPTOELECTRONICS CO., LTD"))
      (libsource (lib "") (part "SK6812-E_1"))
    )
    (comp (ref "D112")
      (value "SK6812-E")
      (footprint "LED_SK6812-E")
      (fields (field (name "MF") "DONGGUANG OPSCO OPTOELECTRONICS CO., LTD"))
      (libsource (lib "") (part "SK6812-E_1"))
    )
    (comp (ref "D113")
      (value "SK6812-E")
      (footprint "LED_SK6812-E")
      (fields (field (name "MF") "DONGGUANG OPSCO OPTOELECTRONICS CO., LTD"))
      (libsource (lib "") (part "SK6812-E_1"))
    )
    (comp (ref "D114")
      (value "SK6812-E")
      (footprint "LED_SK6812-E")
      (fields (field (name "MF") "DONGGUANG OPSCO OPTOELECTRONICS CO., LTD"))
      (libsource (lib "") (part "SK6812-E_1"))
    )
    (comp (ref "D115")
      (value "SK6812-E")
      (footprint "LED_SK6812-E")
      (fields (field (name "MF") "DONGGUANG OPSCO OPTOELECTRONICS CO., LTD"))
      (libsource (lib "") (part "SK6812-E_1"))
    )
    (comp (ref "D116")
      (value "SK6812-E")
      (footprint "LED_SK6812-E")
      (fields (field (name "MF") "DONGGUANG OPSCO OPTOELECTRONICS CO., LTD"))
      (libsource (lib "Schematic-Lib-PhilsLab") (part "SK6812-E"))
    )
    (comp (ref "D117")
      (value "SK6812-E")
      (footprint "LED_SK6812-E")
      (fields (field (name "MF") "DONGGUANG OPSCO OPTOELECTRONICS CO., LTD"))
      (libsource (lib "Schematic-Lib-PhilsLab") (part "SK6812-E"))
    )
    (comp (ref "D118")
      (value "SK6812-E")
      (footprint "LED_SK6812-E")
      (fields (field (name "MF") "DONGGUANG OPSCO OPTOELECTRONICS CO., LTD"))
      (libsource (lib "Schematic-Lib-PhilsLab") (part "SK6812-E"))
    )
    (comp (ref "D119")
      (value "SK6812-E")
      (footprint "LED_SK6812-E")
      (fields (field (name "MF") "DONGGUANG OPSCO OPTOELECTRONICS CO., LTD"))
      (libsource (lib "Schematic-Lib-PhilsLab") (part "SK6812-E"))
    )
    (comp (ref "D120")
      (value "SK6812-E")
      (footprint "LED_SK6812-E")
      (fields (field (name "MF") "DONGGUANG OPSCO OPTOELECTRONICS CO., LTD"))
      (libsource (lib "Schematic-Lib-PhilsLab") (part "SK6812-E"))
    )
    (comp (ref "D121")
      (value "SK6812-E")
      (footprint "LED_SK6812-E")
      (fields (field (name "MF") "DONGGUANG OPSCO OPTOELECTRONICS CO., LTD"))
      (libsource (lib "Schematic-Lib-PhilsLab") (part "SK6812-E"))
    )
    (comp (ref "D122")
      (value "SK6812-E")
      (footprint "LED_SK6812-E")
      (fields (field (name "MF") "DONGGUANG OPSCO OPTOELECTRONICS CO., LTD"))
      (libsource (lib "Schematic-Lib-PhilsLab") (part "SK6812-E"))
    )
    (comp (ref "D123")
      (value "SK6812-E")
      (footprint "LED_SK6812-E")
      (fields (field (name "MF") "DONGGUANG OPSCO OPTOELECTRONICS CO., LTD"))
      (libsource (lib "Schematic-Lib-PhilsLab") (part "SK6812-E"))
    )
    (comp (ref "J1")
      (value "217179-0001")
      (footprint "FP-2171790001-MFG")
      (description "CONN RCP USB2.0 TYP C 24P SMD RA")
      (libsource (lib "Altium Content Vault") (part "8b86497a633d14b3f74642136fc0ce6"))
    )
    (comp (ref "P1")
      (value "SM03B-SRSS-TB")
      (footprint "JST-SM03B-SRSS-TB_V")
      (description "Male Header, Pitch 1 mm, 1 x 3 Position, Height 2.9 mm, -25 to 85 degC, RoHS, Tape and Reel")
      (fields (field (name "MANUFACTURER") "JST"))
      (libsource (lib "Altium Content Vault") (part "CN-1P-2M-R3"))
    )
    (comp (ref "P2")
      (value "SM03B-SRSS-TB")
      (footprint "JST-SM03B-SRSS-TB_V")
      (description "Male Header, Pitch 1 mm, 1 x 3 Position, Height 2.9 mm, -25 to 85 degC, RoHS, Tape and Reel")
      (fields (field (name "MANUFACTURER") "JST"))
      (libsource (lib "Altium Content Vault") (part "CN-1P-2M-R3"))
    )
    (comp (ref "R1")
      (value "DNF")
      (footprint "RES_0402")
      (description "Resistor SMD 0402")
      (libsource (lib "Schematic-Lib-PhilsLab") (part "RES_0402"))
    )
    (comp (ref "R2")
      (value "5k1")
      (footprint "RES_0402")
      (description "Resistor SMD 0402")
      (libsource (lib "Schematic-Lib-PhilsLab") (part "RES_0402"))
    )
    (comp (ref "R3")
      (value "1k")
      (footprint "RES_0402")
      (description "Resistor SMD 0402")
      (libsource (lib "Schematic-Lib-PhilsLab") (part "RES_0402"))
    )
    (comp (ref "R4")
      (value "5k1")
      (footprint "RES_0402")
      (description "Resistor SMD 0402")
      (libsource (lib "Schematic-Lib-PhilsLab") (part "RES_0402"))
    )
    (comp (ref "R5")
      (value "1k")
      (footprint "RES_0402")
      (description "Resistor SMD 0402")
      (libsource (lib "Schematic-Lib-PhilsLab") (part "RES_0402"))
    )
    (comp (ref "R6")
      (value "27")
      (footprint "RES_0402")
      (description "Resistor SMD 0402")
      (libsource (lib "Schematic-Lib-PhilsLab") (part "RES_0402"))
    )
    (comp (ref "R7")
      (value "27")
      (footprint "RES_0402")
      (description "Resistor SMD 0402")
      (libsource (lib "Schematic-Lib-PhilsLab") (part "RES_0402"))
    )
    (comp (ref "S1")
      (value "PG151101S11")
      (footprint "SW_PG151101S11")
      (description "Kailh Hotswap MX Socket")
      (fields (field (name "MF") "Kailh"))
      (libsource (lib "Schematic-Lib-PhilsLab") (part "PG151101S11"))
    )
    (comp (ref "S2")
      (value "PG151101S11")
      (footprint "SW_PG151101S11")
      (description "Kailh Hotswap MX Socket")
      (fields (field (name "MF") "Kailh"))
      (libsource (lib "Schematic-Lib-PhilsLab") (part "PG151101S11"))
    )
    (comp (ref "S3")
      (value "PG151101S11")
      (footprint "SW_PG151101S11")
      (description "Kailh Hotswap MX Socket")
      (fields (field (name "MF") "Kailh"))
      (libsource (lib "Schematic-Lib-PhilsLab") (part "PG151101S11"))
    )
    (comp (ref "S4")
      (value "PG151101S11")
      (footprint "SW_PG151101S11")
      (description "Kailh Hotswap MX Socket")
      (fields (field (name "MF") "Kailh"))
      (libsource (lib "Schematic-Lib-PhilsLab") (part "PG151101S11"))
    )
    (comp (ref "S5")
      (value "PG151101S11")
      (footprint "SW_PG151101S11")
      (description "Kailh Hotswap MX Socket")
      (fields (field (name "MF") "Kailh"))
      (libsource (lib "Schematic-Lib-PhilsLab") (part "PG151101S11"))
    )
    (comp (ref "S6")
      (value "PG151101S11")
      (footprint "SW_PG151101S11")
      (description "Kailh Hotswap MX Socket")
      (fields (field (name "MF") "Kailh"))
      (libsource (lib "Schematic-Lib-PhilsLab") (part "PG151101S11"))
    )
    (comp (ref "S7")
      (value "PG151101S11")
      (footprint "SW_PG151101S11")
      (description "Kailh Hotswap MX Socket")
      (fields (field (name "MF") "Kailh"))
      (libsource (lib "Schematic-Lib-PhilsLab") (part "PG151101S11"))
    )
    (comp (ref "S8")
      (value "PG151101S11")
      (footprint "SW_PG151101S11")
      (description "Kailh Hotswap MX Socket")
      (fields (field (name "MF") "Kailh"))
      (libsource (lib "Schematic-Lib-PhilsLab") (part "PG151101S11"))
    )
    (comp (ref "S9")
      (value "PG151101S11")
      (footprint "SW_PG151101S11")
      (description "Kailh Hotswap MX Socket")
      (fields (field (name "MF") "Kailh"))
      (libsource (lib "Schematic-Lib-PhilsLab") (part "PG151101S11"))
    )
    (comp (ref "S10")
      (value "PG151101S11")
      (footprint "SW_PG151101S11")
      (description "Kailh Hotswap MX Socket")
      (fields (field (name "MF") "Kailh"))
      (libsource (lib "Schematic-Lib-PhilsLab") (part "PG151101S11"))
    )
    (comp (ref "S11")
      (value "PG151101S11")
      (footprint "SW_PG151101S11")
      (description "Kailh Hotswap MX Socket")
      (fields (field (name "MF") "Kailh"))
      (libsource (lib "Schematic-Lib-PhilsLab") (part "PG151101S11"))
    )
    (comp (ref "S12")
      (value "PG151101S11")
      (footprint "SW_PG151101S11")
      (description "Kailh Hotswap MX Socket")
      (fields (field (name "MF") "Kailh"))
      (libsource (lib "Schematic-Lib-PhilsLab") (part "PG151101S11"))
    )
    (comp (ref "S13")
      (value "PG151101S11")
      (footprint "SW_PG151101S11")
      (description "Kailh Hotswap MX Socket")
      (fields (field (name "MF") "Kailh"))
      (libsource (lib "Schematic-Lib-PhilsLab") (part "PG151101S11"))
    )
    (comp (ref "S14")
      (value "PG151101S11")
      (footprint "SW_PG151101S11")
      (description "Kailh Hotswap MX Socket")
      (fields (field (name "MF") "Kailh"))
      (libsource (lib "Schematic-Lib-PhilsLab") (part "PG151101S11"))
    )
    (comp (ref "S15")
      (value "PG151101S11")
      (footprint "SW_PG151101S11")
      (description "Kailh Hotswap MX Socket")
      (fields (field (name "MF") "Kailh"))
      (libsource (lib "Schematic-Lib-PhilsLab") (part "PG151101S11"))
    )
    (comp (ref "S16")
      (value "PG151101S11")
      (footprint "SW_PG151101S11")
      (description "Kailh Hotswap MX Socket")
      (fields (field (name "MF") "Kailh"))
      (libsource (lib "Schematic-Lib-PhilsLab") (part "PG151101S11"))
    )
    (comp (ref "S17")
      (value "PG151101S11")
      (footprint "SW_PG151101S11")
      (description "Kailh Hotswap MX Socket")
      (fields (field (name "MF") "Kailh"))
      (libsource (lib "Schematic-Lib-PhilsLab") (part "PG151101S11"))
    )
    (comp (ref "S18")
      (value "PG151101S11")
      (footprint "SW_PG151101S11")
      (description "Kailh Hotswap MX Socket")
      (fields (field (name "MF") "Kailh"))
      (libsource (lib "Schematic-Lib-PhilsLab") (part "PG151101S11"))
    )
    (comp (ref "S19")
      (value "PG151101S11")
      (footprint "SW_PG151101S11")
      (description "Kailh Hotswap MX Socket")
      (fields (field (name "MF") "Kailh"))
      (libsource (lib "Schematic-Lib-PhilsLab") (part "PG151101S11"))
    )
    (comp (ref "S20")
      (value "PG151101S11")
      (footprint "SW_PG151101S11")
      (description "Kailh Hotswap MX Socket")
      (fields (field (name "MF") "Kailh"))
      (libsource (lib "Schematic-Lib-PhilsLab") (part "PG151101S11"))
    )
    (comp (ref "S21")
      (value "PG151101S11")
      (footprint "SW_PG151101S11")
      (description "Kailh Hotswap MX Socket")
      (fields (field (name "MF") "Kailh"))
      (libsource (lib "Schematic-Lib-PhilsLab") (part "PG151101S11"))
    )
    (comp (ref "S22")
      (value "PG151101S11")
      (footprint "SW_PG151101S11")
      (description "Kailh Hotswap MX Socket")
      (fields (field (name "MF") "Kailh"))
      (libsource (lib "Schematic-Lib-PhilsLab") (part "PG151101S11"))
    )
    (comp (ref "S23")
      (value "PG151101S11")
      (footprint "SW_PG151101S11")
      (description "Kailh Hotswap MX Socket")
      (fields (field (name "MF") "Kailh"))
      (libsource (lib "Schematic-Lib-PhilsLab") (part "PG151101S11"))
    )
    (comp (ref "S24")
      (value "PG151101S11")
      (footprint "SW_PG151101S11")
      (description "Kailh Hotswap MX Socket")
      (fields (field (name "MF") "Kailh"))
      (libsource (lib "Schematic-Lib-PhilsLab") (part "PG151101S11"))
    )
    (comp (ref "S25")
      (value "PG151101S11")
      (footprint "SW_PG151101S11")
      (description "Kailh Hotswap MX Socket")
      (fields (field (name "MF") "Kailh"))
      (libsource (lib "Schematic-Lib-PhilsLab") (part "PG151101S11"))
    )
    (comp (ref "S26")
      (value "PG151101S11")
      (footprint "SW_PG151101S11")
      (description "Kailh Hotswap MX Socket")
      (fields (field (name "MF") "Kailh"))
      (libsource (lib "Schematic-Lib-PhilsLab") (part "PG151101S11"))
    )
    (comp (ref "S27")
      (value "PG151101S11")
      (footprint "SW_PG151101S11")
      (description "Kailh Hotswap MX Socket")
      (fields (field (name "MF") "Kailh"))
      (libsource (lib "Schematic-Lib-PhilsLab") (part "PG151101S11"))
    )
    (comp (ref "S28")
      (value "PG151101S11")
      (footprint "SW_PG151101S11")
      (description "Kailh Hotswap MX Socket")
      (fields (field (name "MF") "Kailh"))
      (libsource (lib "Schematic-Lib-PhilsLab") (part "PG151101S11"))
    )
    (comp (ref "S29")
      (value "PG151101S11")
      (footprint "SW_PG151101S11")
      (description "Kailh Hotswap MX Socket")
      (fields (field (name "MF") "Kailh"))
      (libsource (lib "Schematic-Lib-PhilsLab") (part "PG151101S11"))
    )
    (comp (ref "S30")
      (value "PG151101S11")
      (footprint "SW_PG151101S11")
      (description "Kailh Hotswap MX Socket")
      (fields (field (name "MF") "Kailh"))
      (libsource (lib "Schematic-Lib-PhilsLab") (part "PG151101S11"))
    )
    (comp (ref "S31")
      (value "PG151101S11")
      (footprint "SW_PG151101S11")
      (description "Kailh Hotswap MX Socket")
      (fields (field (name "MF") "Kailh"))
      (libsource (lib "Schematic-Lib-PhilsLab") (part "PG151101S11"))
    )
    (comp (ref "S32")
      (value "PG151101S11")
      (footprint "SW_PG151101S11")
      (description "Kailh Hotswap MX Socket")
      (fields (field (name "MF") "Kailh"))
      (libsource (lib "Schematic-Lib-PhilsLab") (part "PG151101S11"))
    )
    (comp (ref "S33")
      (value "PG151101S11")
      (footprint "SW_PG151101S11")
      (description "Kailh Hotswap MX Socket")
      (fields (field (name "MF") "Kailh"))
      (libsource (lib "Schematic-Lib-PhilsLab") (part "PG151101S11"))
    )
    (comp (ref "S34")
      (value "PG151101S11")
      (footprint "SW_PG151101S11")
      (description "Kailh Hotswap MX Socket")
      (fields (field (name "MF") "Kailh"))
      (libsource (lib "Schematic-Lib-PhilsLab") (part "PG151101S11"))
    )
    (comp (ref "S35")
      (value "PG151101S11")
      (footprint "SW_PG151101S11")
      (description "Kailh Hotswap MX Socket")
      (fields (field (name "MF") "Kailh"))
      (libsource (lib "Schematic-Lib-PhilsLab") (part "PG151101S11"))
    )
    (comp (ref "S36")
      (value "PG151101S11")
      (footprint "SW_PG151101S11")
      (description "Kailh Hotswap MX Socket")
      (fields (field (name "MF") "Kailh"))
      (libsource (lib "Schematic-Lib-PhilsLab") (part "PG151101S11"))
    )
    (comp (ref "S37")
      (value "PG151101S11")
      (footprint "SW_PG151101S11")
      (description "Kailh Hotswap MX Socket")
      (fields (field (name "MF") "Kailh"))
      (libsource (lib "Schematic-Lib-PhilsLab") (part "PG151101S11"))
    )
    (comp (ref "S38")
      (value "PG151101S11")
      (footprint "SW_PG151101S11")
      (description "Kailh Hotswap MX Socket")
      (fields (field (name "MF") "Kailh"))
      (libsource (lib "Schematic-Lib-PhilsLab") (part "PG151101S11"))
    )
    (comp (ref "S39")
      (value "PG151101S11")
      (footprint "SW_PG151101S11")
      (description "Kailh Hotswap MX Socket")
      (fields (field (name "MF") "Kailh"))
      (libsource (lib "Schematic-Lib-PhilsLab") (part "PG151101S11"))
    )
    (comp (ref "S40")
      (value "PG151101S11")
      (footprint "SW_PG151101S11")
      (description "Kailh Hotswap MX Socket")
      (fields (field (name "MF") "Kailh"))
      (libsource (lib "Schematic-Lib-PhilsLab") (part "PG151101S11"))
    )
    (comp (ref "S41")
      (value "PG151101S11")
      (footprint "SW_PG151101S11")
      (description "Kailh Hotswap MX Socket")
      (fields (field (name "MF") "Kailh"))
      (libsource (lib "Schematic-Lib-PhilsLab") (part "PG151101S11"))
    )
    (comp (ref "S42")
      (value "PG151101S11")
      (footprint "SW_PG151101S11")
      (description "Kailh Hotswap MX Socket")
      (fields (field (name "MF") "Kailh"))
      (libsource (lib "Schematic-Lib-PhilsLab") (part "PG151101S11"))
    )
    (comp (ref "S43")
      (value "PG151101S11")
      (footprint "SW_PG151101S11")
      (description "Kailh Hotswap MX Socket")
      (fields (field (name "MF") "Kailh"))
      (libsource (lib "Schematic-Lib-PhilsLab") (part "PG151101S11"))
    )
    (comp (ref "S44")
      (value "PG151101S11")
      (footprint "SW_PG151101S11")
      (description "Kailh Hotswap MX Socket")
      (fields (field (name "MF") "Kailh"))
      (libsource (lib "Schematic-Lib-PhilsLab") (part "PG151101S11"))
    )
    (comp (ref "S45")
      (value "PG151101S11")
      (footprint "SW_PG151101S11")
      (description "Kailh Hotswap MX Socket")
      (fields (field (name "MF") "Kailh"))
      (libsource (lib "Schematic-Lib-PhilsLab") (part "PG151101S11"))
    )
    (comp (ref "S46")
      (value "PG151101S11")
      (footprint "SW_PG151101S11")
      (description "Kailh Hotswap MX Socket")
      (fields (field (name "MF") "Kailh"))
      (libsource (lib "Schematic-Lib-PhilsLab") (part "PG151101S11"))
    )
    (comp (ref "S47")
      (value "PG151101S11")
      (footprint "SW_PG151101S11")
      (description "Kailh Hotswap MX Socket")
      (fields (field (name "MF") "Kailh"))
      (libsource (lib "Schematic-Lib-PhilsLab") (part "PG151101S11"))
    )
    (comp (ref "S48")
      (value "PG151101S11")
      (footprint "SW_PG151101S11")
      (description "Kailh Hotswap MX Socket")
      (fields (field (name "MF") "Kailh"))
      (libsource (lib "Schematic-Lib-PhilsLab") (part "PG151101S11"))
    )
    (comp (ref "S49")
      (value "PG151101S11")
      (footprint "SW_PG151101S11")
      (description "Kailh Hotswap MX Socket")
      (fields (field (name "MF") "Kailh"))
      (libsource (lib "Schematic-Lib-PhilsLab") (part "PG151101S11"))
    )
    (comp (ref "S50")
      (value "PG151101S11")
      (footprint "SW_PG151101S11")
      (description "Kailh Hotswap MX Socket")
      (fields (field (name "MF") "Kailh"))
      (libsource (lib "Schematic-Lib-PhilsLab") (part "PG151101S11"))
    )
    (comp (ref "S51")
      (value "PG151101S11")
      (footprint "SW_PG151101S11")
      (description "Kailh Hotswap MX Socket")
      (fields (field (name "MF") "Kailh"))
      (libsource (lib "Schematic-Lib-PhilsLab") (part "PG151101S11"))
    )
    (comp (ref "S52")
      (value "PG151101S11")
      (footprint "SW_PG151101S11")
      (description "Kailh Hotswap MX Socket")
      (fields (field (name "MF") "Kailh"))
      (libsource (lib "Schematic-Lib-PhilsLab") (part "PG151101S11"))
    )
    (comp (ref "S53")
      (value "PG151101S11")
      (footprint "SW_PG151101S11")
      (description "Kailh Hotswap MX Socket")
      (fields (field (name "MF") "Kailh"))
      (libsource (lib "Schematic-Lib-PhilsLab") (part "PG151101S11"))
    )
    (comp (ref "S54")
      (value "PG151101S11")
      (footprint "SW_PG151101S11")
      (description "Kailh Hotswap MX Socket")
      (fields (field (name "MF") "Kailh"))
      (libsource (lib "Schematic-Lib-PhilsLab") (part "PG151101S11"))
    )
    (comp (ref "S55")
      (value "PG151101S11")
      (footprint "SW_PG151101S11")
      (description "Kailh Hotswap MX Socket")
      (fields (field (name "MF") "Kailh"))
      (libsource (lib "Schematic-Lib-PhilsLab") (part "PG151101S11"))
    )
    (comp (ref "S56")
      (value "PG151101S11")
      (footprint "SW_PG151101S11")
      (description "Kailh Hotswap MX Socket")
      (fields (field (name "MF") "Kailh"))
      (libsource (lib "Schematic-Lib-PhilsLab") (part "PG151101S11"))
    )
    (comp (ref "S57")
      (value "PG151101S11")
      (footprint "SW_PG151101S11")
      (description "Kailh Hotswap MX Socket")
      (fields (field (name "MF") "Kailh"))
      (libsource (lib "Schematic-Lib-PhilsLab") (part "PG151101S11"))
    )
    (comp (ref "S58")
      (value "PG151101S11")
      (footprint "SW_PG151101S11")
      (description "Kailh Hotswap MX Socket")
      (fields (field (name "MF") "Kailh"))
      (libsource (lib "Schematic-Lib-PhilsLab") (part "PG151101S11"))
    )
    (comp (ref "S59")
      (value "PG151101S11")
      (footprint "SW_PG151101S11")
      (description "Kailh Hotswap MX Socket")
      (fields (field (name "MF") "Kailh"))
      (libsource (lib "Schematic-Lib-PhilsLab") (part "PG151101S11"))
    )
    (comp (ref "S60")
      (value "PG151101S11")
      (footprint "SW_PG151101S11")
      (description "Kailh Hotswap MX Socket")
      (fields (field (name "MF") "Kailh"))
      (libsource (lib "Schematic-Lib-PhilsLab") (part "PG151101S11"))
    )
    (comp (ref "S61")
      (value "PG151101S11")
      (footprint "SW_PG151101S11")
      (description "Kailh Hotswap MX Socket")
      (fields (field (name "MF") "Kailh"))
      (libsource (lib "Schematic-Lib-PhilsLab") (part "PG151101S11"))
    )
    (comp (ref "SW1")
      (value "SKRPANE010")
      (footprint "SKRPANE010")
      (description "Tactile Switch SMD SPST")
      (fields (field (name "MANUFACTURER") "Alps Alpine"))
      (libsource (lib "Schematic-Lib-PhilsLab") (part "SKRPANE010"))
    )
    (comp (ref "U1")
      (value "NCP1117DT33RKG")
      (footprint "FP-369C-MFG")
      (description "IC REG LINEAR 3.3V 1A DPAK-3")
      (libsource (lib "Altium Content Vault") (part "42bbf5c8e4ae9854764b07c869d8ce2"))
    )
    (comp (ref "U2")
      (value "RP2040")
      (footprint "QFN-56-EP")
      (description "32-Bit Dual-Core ARM Cortex-M0+ Microcontroller")
      (fields (field (name "MANUFACTURER") "Raspberry Pi"))
      (libsource (lib "Schematic-Lib-PhilsLab") (part "RP2040"))
    )
    (comp (ref "U3")
      (value "W25Q128JVSIM")
      (footprint "SOIC-8")
      (description "128M-BIT\r\nSERIAL FLASH MEMORY WITH\r\nDUAL/QUAD SPI & QPI & DTR SOIC-8")
      (fields (field (name "MANUFACTURER") "Winbond"))
      (libsource (lib "Schematic-Lib-PhilsLab") (part "W25Q128JVSIM"))
    )
    (comp (ref "Y1")
      (value "ABM8-272-T3")
      (footprint "XTAL_ABM8-272-T3")
      (description "12 MHz Â±30ppm Crystal 10pF 50 Ohms 4-SMD, No Lead")
      (fields (field (name "MF") "ABRACON"))
      (libsource (lib "Schematic-Lib-PhilsLab") (part "ABM8-272-T3"))
    )
  )
  (nets
    (net (code "1") (name "+1V1") (class "Default")
      (node (ref "C10") (pin "2") (pinfunction "2_2") (pintype "passive"))
      (node (ref "C11") (pin "2") (pinfunction "2_2") (pintype "passive"))
      (node (ref "C9") (pin "2") (pinfunction "2_2") (pintype "passive"))
      (node (ref "U2") (pin "23") (pinfunction "DVDD_23") (pintype "power_in"))
      (node (ref "U2") (pin "45") (pinfunction "VREG_VOUT_45") (pintype "power_in"))
      (node (ref "U2") (pin "50") (pinfunction "DVDD_50") (pintype "power_in"))
    )
    (net (code "2") (name "+3V3") (class "Default")
      (node (ref "C1") (pin "2") (pinfunction "2_2") (pintype "passive"))
      (node (ref "C13") (pin "2") (pinfunction "2_2") (pintype "passive"))
      (node (ref "C15") (pin "2") (pinfunction "2_2") (pintype "passive"))
      (node (ref "C2") (pin "2") (pinfunction "2_2") (pintype "passive"))
      (node (ref "C3") (pin "2") (pinfunction "2_2") (pintype "passive"))
      (node (ref "C4") (pin "2") (pinfunction "2_2") (pintype "passive"))
      (node (ref "C5") (pin "2") (pinfunction "2_2") (pintype "passive"))
      (node (ref "C6") (pin "2") (pinfunction "2_2") (pintype "passive"))
      (node (ref "C7") (pin "2") (pinfunction "2_2") (pintype "passive"))
      (node (ref "C8") (pin "2") (pinfunction "2_2") (pintype "passive"))
      (node (ref "R1") (pin "1") (pinfunction "1_1") (pintype "passive"))
      (node (ref "U1") (pin "4") (pinfunction "Output_4") (pintype "power_in"))
      (node (ref "U2") (pin "1") (pinfunction "IOVDD_1") (pintype "power_in"))
      (node (ref "U2") (pin "10") (pinfunction "IOVDD_10") (pintype "power_in"))
      (node (ref "U2") (pin "22") (pinfunction "IOVDD_22") (pintype "power_in"))
      (node (ref "U2") (pin "33") (pinfunction "IOVDD_33") (pintype "power_in"))
      (node (ref "U2") (pin "42") (pinfunction "IOVDD_42") (pintype "power_in"))
      (node (ref "U2") (pin "43") (pinfunction "ADC_IOVDD_43") (pintype "power_in"))
      (node (ref "U2") (pin "44") (pinfunction "VREG_IOVDD_44") (pintype "power_in"))
      (node (ref "U2") (pin "48") (pinfunction "USB_IOVDD_48") (pintype "power_in"))
      (node (ref "U2") (pin "49") (pinfunction "IOVDD_49") (pintype "power_in"))
      (node (ref "U3") (pin "8") (pinfunction "VCC_8") (pintype "power_in"))
    )
    (net (code "3") (name "/COL0") (class "Default")
      (node (ref "S1") (pin "1") (pinfunction "1_1") (pintype "passive"))
      (node (ref "S15") (pin "1") (pinfunction "1_1") (pintype "passive"))
      (node (ref "S29") (pin "1") (pinfunction "1_1") (pintype "passive"))
      (node (ref "S42") (pin "1") (pinfunction "1_1") (pintype "passive"))
      (node (ref "S54") (pin "1") (pinfunction "1_1") (pintype "passive"))
      (node (ref "U2") (pin "36") (pinfunction "GPIO24_36") (pintype "bidirectional"))
    )
    (net (code "4") (name "/COL1") (class "Default")
      (node (ref "S16") (pin "1") (pinfunction "1_1") (pintype "passive"))
      (node (ref "S2") (pin "1") (pinfunction "1_1") (pintype "passive"))
      (node (ref "S30") (pin "1") (pinfunction "1_1") (pintype "passive"))
      (node (ref "S43") (pin "1") (pinfunction "1_1") (pintype "passive"))
      (node (ref "S55") (pin "1") (pinfunction "1_1") (pintype "passive"))
      (node (ref "U2") (pin "37") (pinfunction "GPIO25_37") (pintype "bidirectional"))
    )
    (net (code "5") (name "/COL2") (class "Default")
      (node (ref "S17") (pin "1") (pinfunction "1_1") (pintype "passive"))
      (node (ref "S3") (pin "1") (pinfunction "1_1") (pintype "passive"))
      (node (ref "S31") (pin "1") (pinfunction "1_1") (pintype "passive"))
      (node (ref "S44") (pin "1") (pinfunction "1_1") (pintype "passive"))
      (node (ref "S56") (pin "1") (pinfunction "1_1") (pintype "passive"))
      (node (ref "U2") (pin "38") (pinfunction "GPIO26_ADC0_38") (pintype "bidirectional"))
    )
    (net (code "6") (name "/COL3") (class "Default")
      (node (ref "S18") (pin "1") (pinfunction "1_1") (pintype "passive"))
      (node (ref "S32") (pin "1") (pinfunction "1_1") (pintype "passive"))
      (node (ref "S4") (pin "1") (pinfunction "1_1") (pintype "passive"))
      (node (ref "S45") (pin "1") (pinfunction "1_1") (pintype "passive"))
      (node (ref "U2") (pin "7") (pinfunction "GPIO5_7") (pintype "bidirectional"))
    )
    (net (code "7") (name "/COL4") (class "Default")
      (node (ref "S19") (pin "1") (pinfunction "1_1") (pintype "passive"))
      (node (ref "S33") (pin "1") (pinfunction "1_1") (pintype "passive"))
      (node (ref "S46") (pin "1") (pinfunction "1_1") (pintype "passive"))
      (node (ref "S5") (pin "1") (pinfunction "1_1") (pintype "passive"))
      (node (ref "U2") (pin "13") (pinfunction "GPIO10_13") (pintype "bidirectional"))
    )
    (net (code "8") (name "/COL5") (class "Default")
      (node (ref "S20") (pin "1") (pinfunction "1_1") (pintype "passive"))
      (node (ref "S34") (pin "1") (pinfunction "1_1") (pintype "passive"))
      (node (ref "S47") (pin "1") (pinfunction "1_1") (pintype "passive"))
      (node (ref "S57") (pin "1") (pinfunction "1_1") (pintype "passive"))
      (node (ref "S6") (pin "1") (pinfunction "1_1") (pintype "passive"))
      (node (ref "U2") (pin "12") (pinfunction "GPIO9_12") (pintype "bidirectional"))
    )
    (net (code "9") (name "/COL6") (class "Default")
      (node (ref "S21") (pin "1") (pinfunction "1_1") (pintype "passive"))
      (node (ref "S35") (pin "1") (pinfunction "1_1") (pintype "passive"))
      (node (ref "S48") (pin "1") (pinfunction "1_1") (pintype "passive"))
      (node (ref "S7") (pin "1") (pinfunction "1_1") (pintype "passive"))
      (node (ref "U2") (pin "14") (pinfunction "GPIO11_14") (pintype "bidirectional"))
    )
    (net (code "10") (name "/COL7") (class "Default")
      (node (ref "S22") (pin "1") (pinfunction "1_1") (pintype "passive"))
      (node (ref "S36") (pin "1") (pinfunction "1_1") (pintype "passive"))
      (node (ref "S49") (pin "1") (pinfunction "1_1") (pintype "passive"))
      (node (ref "S8") (pin "1") (pinfunction "1_1") (pintype "passive"))
      (node (ref "U2") (pin "16") (pinfunction "GPIO13_16") (pintype "bidirectional"))
    )
    (net (code "11") (name "/COL8") (class "Default")
      (node (ref "S23") (pin "1") (pinfunction "1_1") (pintype "passive"))
      (node (ref "S37") (pin "1") (pinfunction "1_1") (pintype "passive"))
      (node (ref "S50") (pin "1") (pinfunction "1_1") (pintype "passive"))
      (node (ref "S9") (pin "1") (pinfunction "1_1") (pintype "passive"))
      (node (ref "U2") (pin "15") (pinfunction "GPIO12_15") (pintype "bidirectional"))
    )
    (net (code "12") (name "/COL9") (class "Default")
      (node (ref "S10") (pin "1") (pinfunction "1_1") (pintype "passive"))
      (node (ref "S24") (pin "1") (pinfunction "1_1") (pintype "passive"))
      (node (ref "S38") (pin "1") (pinfunction "1_1") (pintype "passive"))
      (node (ref "S51") (pin "1") (pinfunction "1_1") (pintype "passive"))
      (node (ref "S58") (pin "1") (pinfunction "1_1") (pintype "passive"))
      (node (ref "U2") (pin "27") (pinfunction "GPIO16_27") (pintype "bidirectional"))
    )
    (net (code "13") (name "/COL10") (class "Default")
      (node (ref "S11") (pin "1") (pinfunction "1_1") (pintype "passive"))
      (node (ref "S25") (pin "1") (pinfunction "1_1") (pintype "passive"))
      (node (ref "S39") (pin "1") (pinfunction "1_1") (pintype "passive"))
      (node (ref "S52") (pin "1") (pinfunction "1_1") (pintype "passive"))
      (node (ref "S59") (pin "1") (pinfunction "1_1") (pintype "passive"))
      (node (ref "U2") (pin "28") (pinfunction "GPIO17_28") (pintype "bidirectional"))
    )
    (net (code "14") (name "/COL11") (class "Default")
      (node (ref "S12") (pin "1") (pinfunction "1_1") (pintype "passive"))
      (node (ref "S26") (pin "1") (pinfunction "1_1") (pintype "passive"))
      (node (ref "S40") (pin "1") (pinfunction "1_1") (pintype "passive"))
      (node (ref "S60") (pin "1") (pinfunction "1_1") (pintype "passive"))
      (node (ref "U2") (pin "29") (pinfunction "GPIO18_29") (pintype "bidirectional"))
    )
    (net (code "15") (name "/COL12") (class "Default")
      (node (ref "S13") (pin "1") (pinfunction "1_1") (pintype "passive"))
      (node (ref "S27") (pin "1") (pinfunction "1_1") (pintype "passive"))
      (node (ref "U2") (pin "8") (pinfunction "GPIO6_8") (pintype "bidirectional"))
    )
    (net (code "16") (name "/COL13") (class "Default")
      (node (ref "S14") (pin "1") (pinfunction "1_1") (pintype "passive"))
      (node (ref "S28") (pin "1") (pinfunction "1_1") (pintype "passive"))
      (node (ref "S41") (pin "1") (pinfunction "1_1") (pintype "passive"))
      (node (ref "S53") (pin "1") (pinfunction "1_1") (pintype "passive"))
      (node (ref "S61") (pin "1") (pinfunction "1_1") (pintype "passive"))
      (node (ref "U2") (pin "35") (pinfunction "GPIO23_35") (pintype "bidirectional"))
    )
    (net (code "17") (name "/DIN_N") (class "Default")
      (node (ref "D1") (pin "3") (pinfunction "IO2_3") (pintype "bidirectional"))
      (node (ref "J1") (pin "A7") (pinfunction "Dn1_A7") (pintype "bidirectional"))
      (node (ref "J1") (pin "B7") (pinfunction "Dn2_B7") (pintype "bidirectional"))
    )
    (net (code "18") (name "/DIN_P") (class "Default")
      (node (ref "D1") (pin "1") (pinfunction "IO1_1") (pintype "bidirectional"))
      (node (ref "J1") (pin "A6") (pinfunction "Dp1_A6") (pintype "bidirectional"))
      (node (ref "J1") (pin "B6") (pinfunction "Dp2_B6") (pintype "bidirectional"))
    )
    (net (code "19") (name "/DOUT_N") (class "Default")
      (node (ref "R6") (pin "1") (pinfunction "1_1") (pintype "passive"))
      (node (ref "U2") (pin "46") (pinfunction "USB_DM_46") (pintype "bidirectional"))
    )
    (net (code "20") (name "/DOUT_P") (class "Default")
      (node (ref "R7") (pin "2") (pinfunction "2_2") (pintype "passive"))
      (node (ref "U2") (pin "47") (pinfunction "USB_DP_47") (pintype "bidirectional"))
    )
    (net (code "21") (name "/DRES_N") (class "Default")
      (node (ref "D1") (pin "4") (pinfunction "IO2_4") (pintype "bidirectional"))
      (node (ref "R6") (pin "2") (pinfunction "2_2") (pintype "passive"))
    )
    (net (code "22") (name "/DRES_P") (class "Default")
      (node (ref "D1") (pin "6") (pinfunction "IO1_6") (pintype "bidirectional"))
      (node (ref "R7") (pin "1") (pinfunction "1_1") (pintype "passive"))
    )
    (net (code "23") (name "/QSPI_SCLK") (class "Default")
      (node (ref "U2") (pin "52") (pinfunction "QSPI_SCLK_52") (pintype "output"))
      (node (ref "U3") (pin "6") (pinfunction "CLK_6") (pintype "input"))
    )
    (net (code "24") (name "/QSPI_SD0") (class "Default")
      (node (ref "U2") (pin "53") (pinfunction "QSPI_SD0_53") (pintype "bidirectional"))
      (node (ref "U3") (pin "5") (pinfunction "DI_(IO0)_5") (pintype "bidirectional"))
    )
    (net (code "25") (name "/QSPI_SD1") (class "Default")
      (node (ref "U2") (pin "55") (pinfunction "QSPI_SD1_55") (pintype "bidirectional"))
      (node (ref "U3") (pin "2") (pinfunction "DO_(IO1)_2") (pintype "bidirectional"))
    )
    (net (code "26") (name "/QSPI_SD2") (class "Default")
      (node (ref "U2") (pin "54") (pinfunction "QSPI_SD2_54") (pintype "bidirectional"))
      (node (ref "U3") (pin "3") (pinfunction "NWP_(IO2)_3") (pintype "bidirectional"))
    )
    (net (code "27") (name "/QSPI_SD3") (class "Default")
      (node (ref "U2") (pin "51") (pinfunction "QSPI_SD3_51") (pintype "bidirectional"))
      (node (ref "U3") (pin "7") (pinfunction "NHOLD_(IO3)_7") (pintype "bidirectional"))
    )
    (net (code "28") (name "/QSPI_SS") (class "Default")
      (node (ref "R1") (pin "2") (pinfunction "2_2") (pintype "passive"))
      (node (ref "R3") (pin "2") (pinfunction "2_2") (pintype "passive"))
      (node (ref "U2") (pin "56") (pinfunction "QSPI_SS_56") (pintype "output"))
      (node (ref "U3") (pin "1") (pinfunction "NCS_1") (pintype "input"))
    )
    (net (code "29") (name "/RGB") (class "Default")
      (node (ref "D63") (pin "4") (pinfunction "DIN_4") (pintype "input"))
      (node (ref "U2") (pin "41") (pinfunction "GPIO29_ADC3_41") (pintype "bidirectional"))
    )
    (net (code "30") (name "/ROW0") (class "Default")
      (node (ref "D55") (pin "K") (pinfunction "K_K") (pintype "passive"))
      (node (ref "D56") (pin "K") (pinfunction "K_K") (pintype "passive"))
      (node (ref "D57") (pin "K") (pinfunction "K_K") (pintype "passive"))
      (node (ref "D58") (pin "K") (pinfunction "K_K") (pintype "passive"))
      (node (ref "D59") (pin "K") (pinfunction "K_K") (pintype "passive"))
      (node (ref "D60") (pin "K") (pinfunction "K_K") (pintype "passive"))
      (node (ref "D61") (pin "K") (pinfunction "K_K") (pintype "passive"))
      (node (ref "D62") (pin "K") (pinfunction "K_K") (pintype "passive"))
      (node (ref "U2") (pin "30") (pinfunction "GPIO19_30") (pintype "bidirectional"))
    )
    (net (code "31") (name "/ROW1") (class "Default")
      (node (ref "D43") (pin "K") (pinfunction "K_K") (pintype "passive"))
      (node (ref "D44") (pin "K") (pinfunction "K_K") (pintype "passive"))
      (node (ref "D45") (pin "K") (pinfunction "K_K") (pintype "passive"))
      (node (ref "D46") (pin "K") (pinfunction "K_K") (pintype "passive"))
      (node (ref "D47") (pin "K") (pinfunction "K_K") (pintype "passive"))
      (node (ref "D48") (pin "K") (pinfunction "K_K") (pintype "passive"))
      (node (ref "D49") (pin "K") (pinfunction "K_K") (pintype "passive"))
      (node (ref "D50") (pin "K") (pinfunction "K_K") (pintype "passive"))
      (node (ref "D51") (pin "K") (pinfunction "K_K") (pintype "passive"))
      (node (ref "D52") (pin "K") (pinfunction "K_K") (pintype "passive"))
      (node (ref "D53") (pin "K") (pinfunction "K_K") (pintype "passive"))
      (node (ref "D54") (pin "K") (pinfunction "K_K") (pintype "passive"))
      (node (ref "U2") (pin "3") (pinfunction "GPIO1_3") (pintype "bidirectional"))
    )
    (net (code "32") (name "/ROW2") (class "Default")
      (node (ref "D30") (pin "K") (pinfunction "K_K") (pintype "passive"))
      (node (ref "D31") (pin "K") (pinfunction "K_K") (pintype "passive"))
      (node (ref "D32") (pin "K") (pinfunction "K_K") (pintype "passive"))
      (node (ref "D33") (pin "K") (pinfunction "K_K") (pintype "passive"))
      (node (ref "D34") (pin "K") (pinfunction "K_K") (pintype "passive"))
      (node (ref "D35") (pin "K") (pinfunction "K_K") (pintype "passive"))
      (node (ref "D36") (pin "K") (pinfunction "K_K") (pintype "passive"))
      (node (ref "D37") (pin "K") (pinfunction "K_K") (pintype "passive"))
      (node (ref "D38") (pin "K") (pinfunction "K_K") (pintype "passive"))
      (node (ref "D39") (pin "K") (pinfunction "K_K") (pintype "passive"))
      (node (ref "D40") (pin "K") (pinfunction "K_K") (pintype "passive"))
      (node (ref "D41") (pin "K") (pinfunction "K_K") (pintype "passive"))
      (node (ref "D42") (pin "K") (pinfunction "K_K") (pintype "passive"))
      (node (ref "U2") (pin "4") (pinfunction "GPIO2_4") (pintype "bidirectional"))
    )
    (net (code "33") (name "/ROW3") (class "Default")
      (node (ref "D16") (pin "K") (pinfunction "K_K") (pintype "passive"))
      (node (ref "D17") (pin "K") (pinfunction "K_K") (pintype "passive"))
      (node (ref "D18") (pin "K") (pinfunction "K_K") (pintype "passive"))
      (node (ref "D19") (pin "K") (pinfunction "K_K") (pintype "passive"))
      (node (ref "D20") (pin "K") (pinfunction "K_K") (pintype "passive"))
      (node (ref "D21") (pin "K") (pinfunction "K_K") (pintype "passive"))
      (node (ref "D22") (pin "K") (pinfunction "K_K") (pintype "passive"))
      (node (ref "D23") (pin "K") (pinfunction "K_K") (pintype "passive"))
      (node (ref "D24") (pin "K") (pinfunction "K_K") (pintype "passive"))
      (node (ref "D25") (pin "K") (pinfunction "K_K") (pintype "passive"))
      (node (ref "D26") (pin "K") (pinfunction "K_K") (pintype "passive"))
      (node (ref "D27") (pin "K") (pinfunction "K_K") (pintype "passive"))
      (node (ref "D28") (pin "K") (pinfunction "K_K") (pintype "passive"))
      (node (ref "D29") (pin "K") (pinfunction "K_K") (pintype "passive"))
      (node (ref "U2") (pin "5") (pinfunction "GPIO3_5") (pintype "bidirectional"))
    )
    (net (code "34") (name "/ROW4") (class "Default")
      (node (ref "D10") (pin "K") (pinfunction "K_K") (pintype "passive"))
      (node (ref "D11") (pin "K") (pinfunction "K_K") (pintype "passive"))
      (node (ref "D12") (pin "K") (pinfunction "K_K") (pintype "passive"))
      (node (ref "D13") (pin "K") (pinfunction "K_K") (pintype "passive"))
      (node (ref "D14") (pin "K") (pinfunction "K_K") (pintype "passive"))
      (node (ref "D15") (pin "K") (pinfunction "K_K") (pintype "passive"))
      (node (ref "D2") (pin "K") (pinfunction "K_K") (pintype "passive"))
      (node (ref "D3") (pin "K") (pinfunction "K_K") (pintype "passive"))
      (node (ref "D4") (pin "K") (pinfunction "K_K") (pintype "passive"))
      (node (ref "D5") (pin "K") (pinfunction "K_K") (pintype "passive"))
      (node (ref "D6") (pin "K") (pinfunction "K_K") (pintype "passive"))
      (node (ref "D7") (pin "K") (pinfunction "K_K") (pintype "passive"))
      (node (ref "D8") (pin "K") (pinfunction "K_K") (pintype "passive"))
      (node (ref "D9") (pin "K") (pinfunction "K_K") (pintype "passive"))
      (node (ref "U2") (pin "6") (pinfunction "GPIO4_6") (pintype "bidirectional"))
    )
    (net (code "35") (name "/RX") (class "Default")
      (node (ref "P2") (pin "3") (pinfunction "3_3") (pintype "passive"))
      (node (ref "U2") (pin "32") (pinfunction "GPIO21_32") (pintype "bidirectional"))
    )
    (net (code "36") (name "/SWDCLK") (class "Default")
      (node (ref "P1") (pin "1") (pinfunction "1_1") (pintype "passive"))
      (node (ref "U2") (pin "24") (pinfunction "SWCLK_24") (pintype "input"))
    )
    (net (code "37") (name "/SWDIO") (class "Default")
      (node (ref "P1") (pin "3") (pinfunction "3_3") (pintype "passive"))
      (node (ref "U2") (pin "25") (pinfunction "SWD_25") (pintype "bidirectional"))
    )
    (net (code "38") (name "/TX") (class "Default")
      (node (ref "P2") (pin "1") (pinfunction "1_1") (pintype "passive"))
      (node (ref "U2") (pin "31") (pinfunction "GPIO20_31") (pintype "bidirectional"))
    )
    (net (code "39") (name "/XIN") (class "Default")
      (node (ref "C14") (pin "1") (pinfunction "1_1") (pintype "passive"))
      (node (ref "U2") (pin "20") (pinfunction "XIN_20") (pintype "input"))
      (node (ref "Y1") (pin "1") (pinfunction "1_1") (pintype "passive"))
    )
    (net (code "40") (name "/XOUT") (class "Default")
      (node (ref "R5") (pin "1") (pinfunction "1_1") (pintype "passive"))
      (node (ref "U2") (pin "21") (pinfunction "XOUT_21") (pintype "output"))
    )
    (net (code "41") (name "GND") (class "Default")
      (node (ref "C1") (pin "1") (pinfunction "1_1") (pintype "passive"))
      (node (ref "C10") (pin "1") (pinfunction "1_1") (pintype "passive"))
      (node (ref "C11") (pin "1") (pinfunction "1_1") (pintype "passive"))
      (node (ref "C12") (pin "1") (pinfunction "1_1") (pintype "passive"))
      (node (ref "C13") (pin "1") (pinfunction "1_1") (pintype "passive"))
      (node (ref "C14") (pin "2") (pinfunction "2_2") (pintype "passive"))
      (node (ref "C15") (pin "1") (pinfunction "1_1") (pintype "passive"))
      (node (ref "C16") (pin "2") (pinfunction "2_2") (pintype "passive"))
      (node (ref "C17") (pin "1") (pinfunction "1_1") (pintype "passive"))
      (node (ref "C18") (pin "1") (pinfunction "1_1") (pintype "passive"))
      (node (ref "C19") (pin "1") (pinfunction "1_1") (pintype "passive"))
      (node (ref "C2") (pin "1") (pinfunction "1_1") (pintype "passive"))
      (node (ref "C20") (pin "1") (pinfunction "1_1") (pintype "passive"))
      (node (ref "C21") (pin "1") (pinfunction "1_1") (pintype "passive"))
      (node (ref "C22") (pin "1") (pinfunction "1_1") (pintype "passive"))
      (node (ref "C23") (pin "1") (pinfunction "1_1") (pintype "passive"))
      (node (ref "C24") (pin "1") (pinfunction "1_1") (pintype "passive"))
      (node (ref "C25") (pin "1") (pinfunction "1_1") (pintype "passive"))
      (node (ref "C26") (pin "1") (pinfunction "1_1") (pintype "passive"))
      (node (ref "C27") (pin "1") (pinfunction "1_1") (pintype "passive"))
      (node (ref "C28") (pin "1") (pinfunction "1_1") (pintype "passive"))
      (node (ref "C29") (pin "1") (pinfunction "1_1") (pintype "passive"))
      (node (ref "C3") (pin "1") (pinfunction "1_1") (pintype "passive"))
      (node (ref "C30") (pin "1") (pinfunction "1_1") (pintype "passive"))
      (node (ref "C31") (pin "1") (pinfunction "1_1") (pintype "passive"))
      (node (ref "C32") (pin "1") (pinfunction "1_1") (pintype "passive"))
      (node (ref "C33") (pin "1") (pinfunction "1_1") (pintype "passive"))
      (node (ref "C34") (pin "1") (pinfunction "1_1") (pintype "passive"))
      (node (ref "C35") (pin "1") (pinfunction "1_1") (pintype "passive"))
      (node (ref "C36") (pin "1") (pinfunction "1_1") (pintype "passive"))
      (node (ref "C37") (pin "1") (pinfunction "1_1") (pintype "passive"))
      (node (ref "C38") (pin "1") (pinfunction "1_1") (pintype "passive"))
      (node (ref "C39") (pin "1") (pinfunction "1_1") (pintype "passive"))
      (node (ref "C4") (pin "1") (pinfunction "1_1") (pintype "passive"))
      (node (ref "C40") (pin "1") (pinfunction "1_1") (pintype "passive"))
      (node (ref "C41") (pin "1") (pinfunction "1_1") (pintype "passive"))
      (node (ref "C42") (pin "1") (pinfunction "1_1") (pintype "passive"))
      (node (ref "C43") (pin "1") (pinfunction "1_1") (pintype "passive"))
      (node (ref "C44") (pin "1") (pinfunction "1_1") (pintype "passive"))
      (node (ref "C45") (pin "1") (pinfunction "1_1") (pintype "passive"))
      (node (ref "C46") (pin "1") (pinfunction "1_1") (pintype "passive"))
      (node (ref "C47") (pin "1") (pinfunction "1_1") (pintype "passive"))
      (node (ref "C48") (pin "1") (pinfunction "1_1") (pintype "passive"))
      (node (ref "C49") (pin "1") (pinfunction "1_1") (pintype "passive"))
      (node (ref "C5") (pin "1") (pinfunction "1_1") (pintype "passive"))
      (node (ref "C50") (pin "1") (pinfunction "1_1") (pintype "passive"))
      (node (ref "C51") (pin "1") (pinfunction "1_1") (pintype "passive"))
      (node (ref "C52") (pin "1") (pinfunction "1_1") (pintype "passive"))
      (node (ref "C53") (pin "1") (pinfunction "1_1") (pintype "passive"))
      (node (ref "C54") (pin "1") (pinfunction "1_1") (pintype "passive"))
      (node (ref "C55") (pin "1") (pinfunction "1_1") (pintype "passive"))
      (node (ref "C56") (pin "1") (pinfunction "1_1") (pintype "passive"))
      (node (ref "C57") (pin "1") (pinfunction "1_1") (pintype "passive"))
      (node (ref "C58") (pin "1") (pinfunction "1_1") (pintype "passive"))
      (node (ref "C59") (pin "1") (pinfunction "1_1") (pintype "passive"))
      (node (ref "C6") (pin "1") (pinfunction "1_1") (pintype "passive"))
      (node (ref "C60") (pin "1") (pinfunction "1_1") (pintype "passive"))
      (node (ref "C61") (pin "1") (pinfunction "1_1") (pintype "passive"))
      (node (ref "C62") (pin "1") (pinfunction "1_1") (pintype "passive"))
      (node (ref "C63") (pin "1") (pinfunction "1_1") (pintype "passive"))
      (node (ref "C64") (pin "1") (pinfunction "1_1") (pintype "passive"))
      (node (ref "C65") (pin "1") (pinfunction "1_1") (pintype "passive"))
      (node (ref "C66") (pin "1") (pinfunction "1_1") (pintype "passive"))
      (node (ref "C67") (pin "1") (pinfunction "1_1") (pintype "passive"))
      (node (ref "C68") (pin "1") (pinfunction "1_1") (pintype "passive"))
      (node (ref "C69") (pin "1") (pinfunction "1_1") (pintype "passive"))
      (node (ref "C7") (pin "1") (pinfunction "1_1") (pintype "passive"))
      (node (ref "C70") (pin "1") (pinfunction "1_1") (pintype "passive"))
      (node (ref "C71") (pin "1") (pinfunction "1_1") (pintype "passive"))
      (node (ref "C72") (pin "1") (pinfunction "1_1") (pintype "passive"))
      (node (ref "C73") (pin "1") (pinfunction "1_1") (pintype "passive"))
      (node (ref "C74") (pin "1") (pinfunction "1_1") (pintype "passive"))
      (node (ref "C75") (pin "1") (pinfunction "1_1") (pintype "passive"))
      (node (ref "C76") (pin "1") (pinfunction "1_1") (pintype "passive"))
      (node (ref "C77") (pin "1") (pinfunction "1_1") (pintype "passive"))
      (node (ref "C8") (pin "1") (pinfunction "1_1") (pintype "passive"))
      (node (ref "C9") (pin "1") (pinfunction "1_1") (pintype "passive"))
      (node (ref "D1") (pin "2") (pinfunction "GND_2") (pintype "power_in"))
      (node (ref "D100") (pin "3") (pinfunction "GND_3") (pintype "power_in"))
      (node (ref "D101") (pin "3") (pinfunction "GND_3") (pintype "power_in"))
      (node (ref "D102") (pin "3") (pinfunction "GND_3") (pintype "power_in"))
      (node (ref "D103") (pin "3") (pinfunction "GND_3") (pintype "power_in"))
      (node (ref "D104") (pin "1") (pinfunction "VDD_1") (pintype "power_in"))
      (node (ref "D105") (pin "1") (pinfunction "VDD_1") (pintype "power_in"))
      (node (ref "D106") (pin "1") (pinfunction "VDD_1") (pintype "power_in"))
      (node (ref "D107") (pin "1") (pinfunction "VDD_1") (pintype "power_in"))
      (node (ref "D108") (pin "1") (pinfunction "VDD_1") (pintype "power_in"))
      (node (ref "D109") (pin "1") (pinfunction "VDD_1") (pintype "power_in"))
      (node (ref "D110") (pin "1") (pinfunction "VDD_1") (pintype "power_in"))
      (node (ref "D111") (pin "1") (pinfunction "VDD_1") (pintype "power_in"))
      (node (ref "D112") (pin "1") (pinfunction "VDD_1") (pintype "power_in"))
      (node (ref "D113") (pin "1") (pinfunction "VDD_1") (pintype "power_in"))
      (node (ref "D114") (pin "1") (pinfunction "VDD_1") (pintype "power_in"))
      (node (ref "D115") (pin "1") (pinfunction "VDD_1") (pintype "power_in"))
      (node (ref "D116") (pin "3") (pinfunction "GND_3") (pintype "power_in"))
      (node (ref "D117") (pin "3") (pinfunction "GND_3") (pintype "power_in"))
      (node (ref "D118") (pin "3") (pinfunction "GND_3") (pintype "power_in"))
      (node (ref "D119") (pin "3") (pinfunction "GND_3") (pintype "power_in"))
      (node (ref "D120") (pin "3") (pinfunction "GND_3") (pintype "power_in"))
      (node (ref "D121") (pin "3") (pinfunction "GND_3") (pintype "power_in"))
      (node (ref "D122") (pin "3") (pinfunction "GND_3") (pintype "power_in"))
      (node (ref "D123") (pin "3") (pinfunction "GND_3") (pintype "power_in"))
      (node (ref "D63") (pin "3") (pinfunction "GND_3") (pintype "power_in"))
      (node (ref "D64") (pin "3") (pinfunction "GND_3") (pintype "power_in"))
      (node (ref "D65") (pin "3") (pinfunction "GND_3") (pintype "power_in"))
      (node (ref "D66") (pin "3") (pinfunction "GND_3") (pintype "power_in"))
      (node (ref "D67") (pin "3") (pinfunction "GND_3") (pintype "power_in"))
      (node (ref "D68") (pin "3") (pinfunction "GND_3") (pintype "power_in"))
      (node (ref "D69") (pin "3") (pinfunction "GND_3") (pintype "power_in"))
      (node (ref "D70") (pin "3") (pinfunction "GND_3") (pintype "power_in"))
      (node (ref "D71") (pin "3") (pinfunction "GND_3") (pintype "power_in"))
      (node (ref "D72") (pin "3") (pinfunction "GND_3") (pintype "power_in"))
      (node (ref "D73") (pin "3") (pinfunction "GND_3") (pintype "power_in"))
      (node (ref "D74") (pin "3") (pinfunction "GND_3") (pintype "power_in"))
      (node (ref "D75") (pin "3") (pinfunction "GND_3") (pintype "power_in"))
      (node (ref "D76") (pin "3") (pinfunction "GND_3") (pintype "power_in"))
      (node (ref "D77") (pin "1") (pinfunction "VDD_1") (pintype "power_in"))
      (node (ref "D78") (pin "1") (pinfunction "VDD_1") (pintype "power_in"))
      (node (ref "D79") (pin "1") (pinfunction "VDD_1") (pintype "power_in"))
      (node (ref "D80") (pin "1") (pinfunction "VDD_1") (pintype "power_in"))
      (node (ref "D81") (pin "1") (pinfunction "VDD_1") (pintype "power_in"))
      (node (ref "D82") (pin "1") (pinfunction "VDD_1") (pintype "power_in"))
      (node (ref "D83") (pin "1") (pinfunction "VDD_1") (pintype "power_in"))
      (node (ref "D84") (pin "1") (pinfunction "VDD_1") (pintype "power_in"))
      (node (ref "D85") (pin "1") (pinfunction "VDD_1") (pintype "power_in"))
      (node (ref "D86") (pin "1") (pinfunction "VDD_1") (pintype "power_in"))
      (node (ref "D87") (pin "1") (pinfunction "VDD_1") (pintype "power_in"))
      (node (ref "D88") (pin "1") (pinfunction "VDD_1") (pintype "power_in"))
      (node (ref "D89") (pin "1") (pinfunction "VDD_1") (pintype "power_in"))
      (node (ref "D90") (pin "1") (pinfunction "VDD_1") (pintype "power_in"))
      (node (ref "D91") (pin "3") (pinfunction "GND_3") (pintype "power_in"))
      (node (ref "D92") (pin "3") (pinfunction "GND_3") (pintype "power_in"))
      (node (ref "D93") (pin "3") (pinfunction "GND_3") (pintype "power_in"))
      (node (ref "D94") (pin "3") (pinfunction "GND_3") (pintype "power_in"))
      (node (ref "D95") (pin "3") (pinfunction "GND_3") (pintype "power_in"))
      (node (ref "D96") (pin "3") (pinfunction "GND_3") (pintype "power_in"))
      (node (ref "D97") (pin "3") (pinfunction "GND_3") (pintype "power_in"))
      (node (ref "D98") (pin "3") (pinfunction "GND_3") (pintype "power_in"))
      (node (ref "D99") (pin "3") (pinfunction "GND_3") (pintype "power_in"))
      (node (ref "J1") (pin "A1-B12") (pinfunction "GND_A1-B12") (pintype "power_in"))
      (node (ref "J1") (pin "B1-A12") (pinfunction "GND_B1-A12") (pintype "power_in"))
      (node (ref "P1") (pin "2") (pinfunction "2_2") (pintype "passive"))
      (node (ref "P2") (pin "2") (pinfunction "2_2") (pintype "passive"))
      (node (ref "R2") (pin "2") (pinfunction "2_2") (pintype "passive"))
      (node (ref "R4") (pin "2") (pinfunction "2_2") (pintype "passive"))
      (node (ref "SW1") (pin "12") (pintype "passive"))
      (node (ref "U1") (pin "1") (pinfunction "Ground_1") (pintype "power_in"))
      (node (ref "U2") (pin "19") (pinfunction "TESTEN_19") (pintype "input"))
      (node (ref "U2") (pin "57") (pinfunction "EPAD_57") (pintype "power_in"))
      (node (ref "U3") (pin "4") (pinfunction "GND_4") (pintype "power_in"))
      (node (ref "Y1") (pin "2") (pinfunction "GND_2") (pintype "power_in"))
      (node (ref "Y1") (pin "4") (pinfunction "GND_4") (pintype "power_in"))
    )
    (net (code "42") (name "Net-(C16-Pad1)") (class "Default")
      (node (ref "C16") (pin "1") (pinfunction "1_1") (pintype "passive"))
      (node (ref "R5") (pin "2") (pinfunction "2_2") (pintype "passive"))
      (node (ref "Y1") (pin "3") (pinfunction "3_3") (pintype "passive"))
    )
    (net (code "43") (name "Net-(D2-PadA)") (class "Default")
      (node (ref "D2") (pin "A") (pinfunction "A_A") (pintype "passive"))
      (node (ref "S1") (pin "2") (pinfunction "2_2") (pintype "passive"))
    )
    (net (code "44") (name "Net-(D3-PadA)") (class "Default")
      (node (ref "D3") (pin "A") (pinfunction "A_A") (pintype "passive"))
      (node (ref "S2") (pin "2") (pinfunction "2_2") (pintype "passive"))
    )
    (net (code "45") (name "Net-(D4-PadA)") (class "Default")
      (node (ref "D4") (pin "A") (pinfunction "A_A") (pintype "passive"))
      (node (ref "S3") (pin "2") (pinfunction "2_2") (pintype "passive"))
    )
    (net (code "46") (name "Net-(D5-PadA)") (class "Default")
      (node (ref "D5") (pin "A") (pinfunction "A_A") (pintype "passive"))
      (node (ref "S4") (pin "2") (pinfunction "2_2") (pintype "passive"))
    )
    (net (code "47") (name "Net-(D6-PadA)") (class "Default")
      (node (ref "D6") (pin "A") (pinfunction "A_A") (pintype "passive"))
      (node (ref "S5") (pin "2") (pinfunction "2_2") (pintype "passive"))
    )
    (net (code "48") (name "Net-(D7-PadA)") (class "Default")
      (node (ref "D7") (pin "A") (pinfunction "A_A") (pintype "passive"))
      (node (ref "S6") (pin "2") (pinfunction "2_2") (pintype "passive"))
    )
    (net (code "49") (name "Net-(D8-PadA)") (class "Default")
      (node (ref "D8") (pin "A") (pinfunction "A_A") (pintype "passive"))
      (node (ref "S7") (pin "2") (pinfunction "2_2") (pintype "passive"))
    )
    (net (code "50") (name "Net-(D9-PadA)") (class "Default")
      (node (ref "D9") (pin "A") (pinfunction "A_A") (pintype "passive"))
      (node (ref "S8") (pin "2") (pinfunction "2_2") (pintype "passive"))
    )
    (net (code "51") (name "Net-(D10-PadA)") (class "Default")
      (node (ref "D10") (pin "A") (pinfunction "A_A") (pintype "passive"))
      (node (ref "S9") (pin "2") (pinfunction "2_2") (pintype "passive"))
    )
    (net (code "52") (name "Net-(D11-PadA)") (class "Default")
      (node (ref "D11") (pin "A") (pinfunction "A_A") (pintype "passive"))
      (node (ref "S10") (pin "2") (pinfunction "2_2") (pintype "passive"))
    )
    (net (code "53") (name "Net-(D12-PadA)") (class "Default")
      (node (ref "D12") (pin "A") (pinfunction "A_A") (pintype "passive"))
      (node (ref "S11") (pin "2") (pinfunction "2_2") (pintype "passive"))
    )
    (net (code "54") (name "Net-(D13-PadA)") (class "Default")
      (node (ref "D13") (pin "A") (pinfunction "A_A") (pintype "passive"))
      (node (ref "S12") (pin "2") (pinfunction "2_2") (pintype "passive"))
    )
    (net (code "55") (name "Net-(D14-PadA)") (class "Default")
      (node (ref "D14") (pin "A") (pinfunction "A_A") (pintype "passive"))
      (node (ref "S13") (pin "2") (pinfunction "2_2") (pintype "passive"))
    )
    (net (code "56") (name "Net-(D15-PadA)") (class "Default")
      (node (ref "D15") (pin "A") (pinfunction "A_A") (pintype "passive"))
      (node (ref "S14") (pin "2") (pinfunction "2_2") (pintype "passive"))
    )
    (net (code "57") (name "Net-(D16-PadA)") (class "Default")
      (node (ref "D16") (pin "A") (pinfunction "A_A") (pintype "passive"))
      (node (ref "S15") (pin "2") (pinfunction "2_2") (pintype "passive"))
    )
    (net (code "58") (name "Net-(D17-PadA)") (class "Default")
      (node (ref "D17") (pin "A") (pinfunction "A_A") (pintype "passive"))
      (node (ref "S16") (pin "2") (pinfunction "2_2") (pintype "passive"))
    )
    (net (code "59") (name "Net-(D18-PadA)") (class "Default")
      (node (ref "D18") (pin "A") (pinfunction "A_A") (pintype "passive"))
      (node (ref "S17") (pin "2") (pinfunction "2_2") (pintype "passive"))
    )
    (net (code "60") (name "Net-(D19-PadA)") (class "Default")
      (node (ref "D19") (pin "A") (pinfunction "A_A") (pintype "passive"))
      (node (ref "S18") (pin "2") (pinfunction "2_2") (pintype "passive"))
    )
    (net (code "61") (name "Net-(D20-PadA)") (class "Default")
      (node (ref "D20") (pin "A") (pinfunction "A_A") (pintype "passive"))
      (node (ref "S19") (pin "2") (pinfunction "2_2") (pintype "passive"))
    )
    (net (code "62") (name "Net-(D21-PadA)") (class "Default")
      (node (ref "D21") (pin "A") (pinfunction "A_A") (pintype "passive"))
      (node (ref "S20") (pin "2") (pinfunction "2_2") (pintype "passive"))
    )
    (net (code "63") (name "Net-(D22-PadA)") (class "Default")
      (node (ref "D22") (pin "A") (pinfunction "A_A") (pintype "passive"))
      (node (ref "S21") (pin "2") (pinfunction "2_2") (pintype "passive"))
    )
    (net (code "64") (name "Net-(D23-PadA)") (class "Default")
      (node (ref "D23") (pin "A") (pinfunction "A_A") (pintype "passive"))
      (node (ref "S22") (pin "2") (pinfunction "2_2") (pintype "passive"))
    )
    (net (code "65") (name "Net-(D24-PadA)") (class "Default")
      (node (ref "D24") (pin "A") (pinfunction "A_A") (pintype "passive"))
      (node (ref "S23") (pin "2") (pinfunction "2_2") (pintype "passive"))
    )
    (net (code "66") (name "Net-(D25-PadA)") (class "Default")
      (node (ref "D25") (pin "A") (pinfunction "A_A") (pintype "passive"))
      (node (ref "S24") (pin "2") (pinfunction "2_2") (pintype "passive"))
    )
    (net (code "67") (name "Net-(D26-PadA)") (class "Default")
      (node (ref "D26") (pin "A") (pinfunction "A_A") (pintype "passive"))
      (node (ref "S25") (pin "2") (pinfunction "2_2") (pintype "passive"))
    )
    (net (code "68") (name "Net-(D27-PadA)") (class "Default")
      (node (ref "D27") (pin "A") (pinfunction "A_A") (pintype "passive"))
      (node (ref "S26") (pin "2") (pinfunction "2_2") (pintype "passive"))
    )
    (net (code "69") (name "Net-(D28-PadA)") (class "Default")
      (node (ref "D28") (pin "A") (pinfunction "A_A") (pintype "passive"))
      (node (ref "S27") (pin "2") (pinfunction "2_2") (pintype "passive"))
    )
    (net (code "70") (name "Net-(D29-PadA)") (class "Default")
      (node (ref "D29") (pin "A") (pinfunction "A_A") (pintype "passive"))
      (node (ref "S28") (pin "2") (pinfunction "2_2") (pintype "passive"))
    )
    (net (code "71") (name "Net-(D30-PadA)") (class "Default")
      (node (ref "D30") (pin "A") (pinfunction "A_A") (pintype "passive"))
      (node (ref "S29") (pin "2") (pinfunction "2_2") (pintype "passive"))
    )
    (net (code "72") (name "Net-(D31-PadA)") (class "Default")
      (node (ref "D31") (pin "A") (pinfunction "A_A") (pintype "passive"))
      (node (ref "S30") (pin "2") (pinfunction "2_2") (pintype "passive"))
    )
    (net (code "73") (name "Net-(D32-PadA)") (class "Default")
      (node (ref "D32") (pin "A") (pinfunction "A_A") (pintype "passive"))
      (node (ref "S31") (pin "2") (pinfunction "2_2") (pintype "passive"))
    )
    (net (code "74") (name "Net-(D33-PadA)") (class "Default")
      (node (ref "D33") (pin "A") (pinfunction "A_A") (pintype "passive"))
      (node (ref "S32") (pin "2") (pinfunction "2_2") (pintype "passive"))
    )
    (net (code "75") (name "Net-(D34-PadA)") (class "Default")
      (node (ref "D34") (pin "A") (pinfunction "A_A") (pintype "passive"))
      (node (ref "S33") (pin "2") (pinfunction "2_2") (pintype "passive"))
    )
    (net (code "76") (name "Net-(D35-PadA)") (class "Default")
      (node (ref "D35") (pin "A") (pinfunction "A_A") (pintype "passive"))
      (node (ref "S34") (pin "2") (pinfunction "2_2") (pintype "passive"))
    )
    (net (code "77") (name "Net-(D36-PadA)") (class "Default")
      (node (ref "D36") (pin "A") (pinfunction "A_A") (pintype "passive"))
      (node (ref "S35") (pin "2") (pinfunction "2_2") (pintype "passive"))
    )
    (net (code "78") (name "Net-(D37-PadA)") (class "Default")
      (node (ref "D37") (pin "A") (pinfunction "A_A") (pintype "passive"))
      (node (ref "S36") (pin "2") (pinfunction "2_2") (pintype "passive"))
    )
    (net (code "79") (name "Net-(D38-PadA)") (class "Default")
      (node (ref "D38") (pin "A") (pinfunction "A_A") (pintype "passive"))
      (node (ref "S37") (pin "2") (pinfunction "2_2") (pintype "passive"))
    )
    (net (code "80") (name "Net-(D39-PadA)") (class "Default")
      (node (ref "D39") (pin "A") (pinfunction "A_A") (pintype "passive"))
      (node (ref "S38") (pin "2") (pinfunction "2_2") (pintype "passive"))
    )
    (net (code "81") (name "Net-(D40-PadA)") (class "Default")
      (node (ref "D40") (pin "A") (pinfunction "A_A") (pintype "passive"))
      (node (ref "S39") (pin "2") (pinfunction "2_2") (pintype "passive"))
    )
    (net (code "82") (name "Net-(D41-PadA)") (class "Default")
      (node (ref "D41") (pin "A") (pinfunction "A_A") (pintype "passive"))
      (node (ref "S40") (pin "2") (pinfunction "2_2") (pintype "passive"))
    )
    (net (code "83") (name "Net-(D42-PadA)") (class "Default")
      (node (ref "D42") (pin "A") (pinfunction "A_A") (pintype "passive"))
      (node (ref "S41") (pin "2") (pinfunction "2_2") (pintype "passive"))
    )
    (net (code "84") (name "Net-(D43-PadA)") (class "Default")
      (node (ref "D43") (pin "A") (pinfunction "A_A") (pintype "passive"))
      (node (ref "S42") (pin "2") (pinfunction "2_2") (pintype "passive"))
    )
    (net (code "85") (name "Net-(D44-PadA)") (class "Default")
      (node (ref "D44") (pin "A") (pinfunction "A_A") (pintype "passive"))
      (node (ref "S43") (pin "2") (pinfunction "2_2") (pintype "passive"))
    )
    (net (code "86") (name "Net-(D45-PadA)") (class "Default")
      (node (ref "D45") (pin "A") (pinfunction "A_A") (pintype "passive"))
      (node (ref "S44") (pin "2") (pinfunction "2_2") (pintype "passive"))
    )
    (net (code "87") (name "Net-(D46-PadA)") (class "Default")
      (node (ref "D46") (pin "A") (pinfunction "A_A") (pintype "passive"))
      (node (ref "S45") (pin "2") (pinfunction "2_2") (pintype "passive"))
    )
    (net (code "88") (name "Net-(D47-PadA)") (class "Default")
      (node (ref "D47") (pin "A") (pinfunction "A_A") (pintype "passive"))
      (node (ref "S46") (pin "2") (pinfunction "2_2") (pintype "passive"))
    )
    (net (code "89") (name "Net-(D48-PadA)") (class "Default")
      (node (ref "D48") (pin "A") (pinfunction "A_A") (pintype "passive"))
      (node (ref "S47") (pin "2") (pinfunction "2_2") (pintype "passive"))
    )
    (net (code "90") (name "Net-(D49-PadA)") (class "Default")
      (node (ref "D49") (pin "A") (pinfunction "A_A") (pintype "passive"))
      (node (ref "S48") (pin "2") (pinfunction "2_2") (pintype "passive"))
    )
    (net (code "91") (name "Net-(D50-PadA)") (class "Default")
      (node (ref "D50") (pin "A") (pinfunction "A_A") (pintype "passive"))
      (node (ref "S49") (pin "2") (pinfunction "2_2") (pintype "passive"))
    )
    (net (code "92") (name "Net-(D51-PadA)") (class "Default")
      (node (ref "D51") (pin "A") (pinfunction "A_A") (pintype "passive"))
      (node (ref "S50") (pin "2") (pinfunction "2_2") (pintype "passive"))
    )
    (net (code "93") (name "Net-(D52-PadA)") (class "Default")
      (node (ref "D52") (pin "A") (pinfunction "A_A") (pintype "passive"))
      (node (ref "S51") (pin "2") (pinfunction "2_2") (pintype "passive"))
    )
    (net (code "94") (name "Net-(D53-PadA)") (class "Default")
      (node (ref "D53") (pin "A") (pinfunction "A_A") (pintype "passive"))
      (node (ref "S52") (pin "2") (pinfunction "2_2") (pintype "passive"))
    )
    (net (code "95") (name "Net-(D54-PadA)") (class "Default")
      (node (ref "D54") (pin "A") (pinfunction "A_A") (pintype "passive"))
      (node (ref "S53") (pin "2") (pinfunction "2_2") (pintype "passive"))
    )
    (net (code "96") (name "Net-(D55-PadA)") (class "Default")
      (node (ref "D55") (pin "A") (pinfunction "A_A") (pintype "passive"))
      (node (ref "S54") (pin "2") (pinfunction "2_2") (pintype "passive"))
    )
    (net (code "97") (name "Net-(D56-PadA)") (class "Default")
      (node (ref "D56") (pin "A") (pinfunction "A_A") (pintype "passive"))
      (node (ref "S55") (pin "2") (pinfunction "2_2") (pintype "passive"))
    )
    (net (code "98") (name "Net-(D57-PadA)") (class "Default")
      (node (ref "D57") (pin "A") (pinfunction "A_A") (pintype "passive"))
      (node (ref "S56") (pin "2") (pinfunction "2_2") (pintype "passive"))
    )
    (net (code "99") (name "Net-(D58-PadA)") (class "Default")
      (node (ref "D58") (pin "A") (pinfunction "A_A") (pintype "passive"))
      (node (ref "S57") (pin "2") (pinfunction "2_2") (pintype "passive"))
    )
    (net (code "100") (name "Net-(D59-PadA)") (class "Default")
      (node (ref "D59") (pin "A") (pinfunction "A_A") (pintype "passive"))
      (node (ref "S58") (pin "2") (pinfunction "2_2") (pintype "passive"))
    )
    (net (code "101") (name "Net-(D60-PadA)") (class "Default")
      (node (ref "D60") (pin "A") (pinfunction "A_A") (pintype "passive"))
      (node (ref "S59") (pin "2") (pinfunction "2_2") (pintype "passive"))
    )
    (net (code "102") (name "Net-(D61-PadA)") (class "Default")
      (node (ref "D61") (pin "A") (pinfunction "A_A") (pintype "passive"))
      (node (ref "S60") (pin "2") (pinfunction "2_2") (pintype "passive"))
    )
    (net (code "103") (name "Net-(D62-PadA)") (class "Default")
      (node (ref "D62") (pin "A") (pinfunction "A_A") (pintype "passive"))
      (node (ref "S61") (pin "2") (pinfunction "2_2") (pintype "passive"))
    )
    (net (code "104") (name "Net-(D63-DOUT)") (class "Default")
      (node (ref "D63") (pin "2") (pinfunction "DOUT_2") (pintype "output"))
      (node (ref "D64") (pin "4") (pinfunction "DIN_4") (pintype "input"))
    )
    (net (code "105") (name "Net-(D64-DOUT)") (class "Default")
      (node (ref "D64") (pin "2") (pinfunction "DOUT_2") (pintype "output"))
      (node (ref "D65") (pin "4") (pinfunction "DIN_4") (pintype "input"))
    )
    (net (code "106") (name "Net-(D65-DOUT)") (class "Default")
      (node (ref "D65") (pin "2") (pinfunction "DOUT_2") (pintype "output"))
      (node (ref "D66") (pin "4") (pinfunction "DIN_4") (pintype "input"))
    )
    (net (code "107") (name "Net-(D66-DOUT)") (class "Default")
      (node (ref "D66") (pin "2") (pinfunction "DOUT_2") (pintype "output"))
      (node (ref "D67") (pin "4") (pinfunction "DIN_4") (pintype "input"))
    )
    (net (code "108") (name "Net-(D67-DOUT)") (class "Default")
      (node (ref "D67") (pin "2") (pinfunction "DOUT_2") (pintype "output"))
      (node (ref "D68") (pin "4") (pinfunction "DIN_4") (pintype "input"))
    )
    (net (code "109") (name "Net-(D68-DOUT)") (class "Default")
      (node (ref "D68") (pin "2") (pinfunction "DOUT_2") (pintype "output"))
      (node (ref "D69") (pin "4") (pinfunction "DIN_4") (pintype "input"))
    )
    (net (code "110") (name "Net-(D69-DOUT)") (class "Default")
      (node (ref "D69") (pin "2") (pinfunction "DOUT_2") (pintype "output"))
      (node (ref "D70") (pin "4") (pinfunction "DIN_4") (pintype "input"))
    )
    (net (code "111") (name "Net-(D70-DOUT)") (class "Default")
      (node (ref "D70") (pin "2") (pinfunction "DOUT_2") (pintype "output"))
      (node (ref "D71") (pin "4") (pinfunction "DIN_4") (pintype "input"))
    )
    (net (code "112") (name "Net-(D71-DOUT)") (class "Default")
      (node (ref "D71") (pin "2") (pinfunction "DOUT_2") (pintype "output"))
      (node (ref "D72") (pin "4") (pinfunction "DIN_4") (pintype "input"))
    )
    (net (code "113") (name "Net-(D72-DOUT)") (class "Default")
      (node (ref "D72") (pin "2") (pinfunction "DOUT_2") (pintype "output"))
      (node (ref "D73") (pin "4") (pinfunction "DIN_4") (pintype "input"))
    )
    (net (code "114") (name "Net-(D73-DOUT)") (class "Default")
      (node (ref "D73") (pin "2") (pinfunction "DOUT_2") (pintype "output"))
      (node (ref "D74") (pin "4") (pinfunction "DIN_4") (pintype "input"))
    )
    (net (code "115") (name "Net-(D74-DOUT)") (class "Default")
      (node (ref "D74") (pin "2") (pinfunction "DOUT_2") (pintype "output"))
      (node (ref "D75") (pin "4") (pinfunction "DIN_4") (pintype "input"))
    )
    (net (code "116") (name "Net-(D75-DOUT)") (class "Default")
      (node (ref "D75") (pin "2") (pinfunction "DOUT_2") (pintype "output"))
      (node (ref "D76") (pin "4") (pinfunction "DIN_4") (pintype "input"))
    )
    (net (code "117") (name "Net-(D76-DOUT)") (class "Default")
      (node (ref "D76") (pin "2") (pinfunction "DOUT_2") (pintype "output"))
      (node (ref "D90") (pin "4") (pinfunction "DIN_4") (pintype "input"))
    )
    (net (code "118") (name "Net-(D77-DIN)") (class "Default")
      (node (ref "D77") (pin "4") (pinfunction "DIN_4") (pintype "input"))
      (node (ref "D78") (pin "2") (pinfunction "DOUT_2") (pintype "output"))
    )
    (net (code "119") (name "Net-(D77-DOUT)") (class "Default")
      (node (ref "D77") (pin "2") (pinfunction "DOUT_2") (pintype "output"))
      (node (ref "D91") (pin "4") (pinfunction "DIN_4") (pintype "input"))
    )
    (net (code "120") (name "Net-(D78-DIN)") (class "Default")
      (node (ref "D78") (pin "4") (pinfunction "DIN_4") (pintype "input"))
      (node (ref "D79") (pin "2") (pinfunction "DOUT_2") (pintype "output"))
    )
    (net (code "121") (name "Net-(D79-DIN)") (class "Default")
      (node (ref "D79") (pin "4") (pinfunction "DIN_4") (pintype "input"))
      (node (ref "D80") (pin "2") (pinfunction "DOUT_2") (pintype "output"))
    )
    (net (code "122") (name "Net-(D80-DIN)") (class "Default")
      (node (ref "D80") (pin "4") (pinfunction "DIN_4") (pintype "input"))
      (node (ref "D81") (pin "2") (pinfunction "DOUT_2") (pintype "output"))
    )
    (net (code "123") (name "Net-(D81-DIN)") (class "Default")
      (node (ref "D81") (pin "4") (pinfunction "DIN_4") (pintype "input"))
      (node (ref "D82") (pin "2") (pinfunction "DOUT_2") (pintype "output"))
    )
    (net (code "124") (name "Net-(D82-DIN)") (class "Default")
      (node (ref "D82") (pin "4") (pinfunction "DIN_4") (pintype "input"))
      (node (ref "D83") (pin "2") (pinfunction "DOUT_2") (pintype "output"))
    )
    (net (code "125") (name "Net-(D83-DIN)") (class "Default")
      (node (ref "D83") (pin "4") (pinfunction "DIN_4") (pintype "input"))
      (node (ref "D84") (pin "2") (pinfunction "DOUT_2") (pintype "output"))
    )
    (net (code "126") (name "Net-(D84-DIN)") (class "Default")
      (node (ref "D84") (pin "4") (pinfunction "DIN_4") (pintype "input"))
      (node (ref "D85") (pin "2") (pinfunction "DOUT_2") (pintype "output"))
    )
    (net (code "127") (name "Net-(D85-DIN)") (class "Default")
      (node (ref "D85") (pin "4") (pinfunction "DIN_4") (pintype "input"))
      (node (ref "D86") (pin "2") (pinfunction "DOUT_2") (pintype "output"))
    )
    (net (code "128") (name "Net-(D86-DIN)") (class "Default")
      (node (ref "D86") (pin "4") (pinfunction "DIN_4") (pintype "input"))
      (node (ref "D87") (pin "2") (pinfunction "DOUT_2") (pintype "output"))
    )
    (net (code "129") (name "Net-(D87-DIN)") (class "Default")
      (node (ref "D87") (pin "4") (pinfunction "DIN_4") (pintype "input"))
      (node (ref "D88") (pin "2") (pinfunction "DOUT_2") (pintype "output"))
    )
    (net (code "130") (name "Net-(D88-DIN)") (class "Default")
      (node (ref "D88") (pin "4") (pinfunction "DIN_4") (pintype "input"))
      (node (ref "D89") (pin "2") (pinfunction "DOUT_2") (pintype "output"))
    )
    (net (code "131") (name "Net-(D89-DIN)") (class "Default")
      (node (ref "D89") (pin "4") (pinfunction "DIN_4") (pintype "input"))
      (node (ref "D90") (pin "2") (pinfunction "DOUT_2") (pintype "output"))
    )
    (net (code "132") (name "Net-(D91-DOUT)") (class "Default")
      (node (ref "D91") (pin "2") (pinfunction "DOUT_2") (pintype "output"))
      (node (ref "D92") (pin "4") (pinfunction "DIN_4") (pintype "input"))
    )
    (net (code "133") (name "Net-(D92-DOUT)") (class "Default")
      (node (ref "D92") (pin "2") (pinfunction "DOUT_2") (pintype "output"))
      (node (ref "D93") (pin "4") (pinfunction "DIN_4") (pintype "input"))
    )
    (net (code "134") (name "Net-(D93-DOUT)") (class "Default")
      (node (ref "D93") (pin "2") (pinfunction "DOUT_2") (pintype "output"))
      (node (ref "D94") (pin "4") (pinfunction "DIN_4") (pintype "input"))
    )
    (net (code "135") (name "Net-(D94-DOUT)") (class "Default")
      (node (ref "D94") (pin "2") (pinfunction "DOUT_2") (pintype "output"))
      (node (ref "D95") (pin "4") (pinfunction "DIN_4") (pintype "input"))
    )
    (net (code "136") (name "Net-(D95-DOUT)") (class "Default")
      (node (ref "D95") (pin "2") (pinfunction "DOUT_2") (pintype "output"))
      (node (ref "D96") (pin "4") (pinfunction "DIN_4") (pintype "input"))
    )
    (net (code "137") (name "Net-(D96-DOUT)") (class "Default")
      (node (ref "D96") (pin "2") (pinfunction "DOUT_2") (pintype "output"))
      (node (ref "D97") (pin "4") (pinfunction "DIN_4") (pintype "input"))
    )
    (net (code "138") (name "Net-(D97-DOUT)") (class "Default")
      (node (ref "D97") (pin "2") (pinfunction "DOUT_2") (pintype "output"))
      (node (ref "D98") (pin "4") (pinfunction "DIN_4") (pintype "input"))
    )
    (net (code "139") (name "Net-(D98-DOUT)") (class "Default")
      (node (ref "D98") (pin "2") (pinfunction "DOUT_2") (pintype "output"))
      (node (ref "D99") (pin "4") (pinfunction "DIN_4") (pintype "input"))
    )
    (net (code "140") (name "Net-(D100-DIN)") (class "Default")
      (node (ref "D100") (pin "4") (pinfunction "DIN_4") (pintype "input"))
      (node (ref "D99") (pin "2") (pinfunction "DOUT_2") (pintype "output"))
    )
    (net (code "141") (name "Net-(D100-DOUT)") (class "Default")
      (node (ref "D100") (pin "2") (pinfunction "DOUT_2") (pintype "output"))
      (node (ref "D101") (pin "4") (pinfunction "DIN_4") (pintype "input"))
    )
    (net (code "142") (name "Net-(D101-DOUT)") (class "Default")
      (node (ref "D101") (pin "2") (pinfunction "DOUT_2") (pintype "output"))
      (node (ref "D102") (pin "4") (pinfunction "DIN_4") (pintype "input"))
    )
    (net (code "143") (name "Net-(D102-DOUT)") (class "Default")
      (node (ref "D102") (pin "2") (pinfunction "DOUT_2") (pintype "output"))
      (node (ref "D103") (pin "4") (pinfunction "DIN_4") (pintype "input"))
    )
    (net (code "144") (name "Net-(D103-DOUT)") (class "Default")
      (node (ref "D103") (pin "2") (pinfunction "DOUT_2") (pintype "output"))
      (node (ref "D115") (pin "4") (pinfunction "DIN_4") (pintype "input"))
    )
    (net (code "145") (name "Net-(D104-DIN)") (class "Default")
      (node (ref "D104") (pin "4") (pinfunction "DIN_4") (pintype "input"))
      (node (ref "D105") (pin "2") (pinfunction "DOUT_2") (pintype "output"))
    )
    (net (code "146") (name "Net-(D104-DOUT)") (class "Default")
      (node (ref "D104") (pin "2") (pinfunction "DOUT_2") (pintype "output"))
      (node (ref "D116") (pin "4") (pinfunction "DIN_4") (pintype "input"))
    )
    (net (code "147") (name "Net-(D105-DIN)") (class "Default")
      (node (ref "D105") (pin "4") (pinfunction "DIN_4") (pintype "input"))
      (node (ref "D106") (pin "2") (pinfunction "DOUT_2") (pintype "output"))
    )
    (net (code "148") (name "Net-(D106-DIN)") (class "Default")
      (node (ref "D106") (pin "4") (pinfunction "DIN_4") (pintype "input"))
      (node (ref "D107") (pin "2") (pinfunction "DOUT_2") (pintype "output"))
    )
    (net (code "149") (name "Net-(D107-DIN)") (class "Default")
      (node (ref "D107") (pin "4") (pinfunction "DIN_4") (pintype "input"))
      (node (ref "D108") (pin "2") (pinfunction "DOUT_2") (pintype "output"))
    )
    (net (code "150") (name "Net-(D108-DIN)") (class "Default")
      (node (ref "D108") (pin "4") (pinfunction "DIN_4") (pintype "input"))
      (node (ref "D109") (pin "2") (pinfunction "DOUT_2") (pintype "output"))
    )
    (net (code "151") (name "Net-(D109-DIN)") (class "Default")
      (node (ref "D109") (pin "4") (pinfunction "DIN_4") (pintype "input"))
      (node (ref "D110") (pin "2") (pinfunction "DOUT_2") (pintype "output"))
    )
    (net (code "152") (name "Net-(D110-DIN)") (class "Default")
      (node (ref "D110") (pin "4") (pinfunction "DIN_4") (pintype "input"))
      (node (ref "D111") (pin "2") (pinfunction "DOUT_2") (pintype "output"))
    )
    (net (code "153") (name "Net-(D111-DIN)") (class "Default")
      (node (ref "D111") (pin "4") (pinfunction "DIN_4") (pintype "input"))
      (node (ref "D112") (pin "2") (pinfunction "DOUT_2") (pintype "output"))
    )
    (net (code "154") (name "Net-(D112-DIN)") (class "Default")
      (node (ref "D112") (pin "4") (pinfunction "DIN_4") (pintype "input"))
      (node (ref "D113") (pin "2") (pinfunction "DOUT_2") (pintype "output"))
    )
    (net (code "155") (name "Net-(D113-DIN)") (class "Default")
      (node (ref "D113") (pin "4") (pinfunction "DIN_4") (pintype "input"))
      (node (ref "D114") (pin "2") (pinfunction "DOUT_2") (pintype "output"))
    )
    (net (code "156") (name "Net-(D114-DIN)") (class "Default")
      (node (ref "D114") (pin "4") (pinfunction "DIN_4") (pintype "input"))
      (node (ref "D115") (pin "2") (pinfunction "DOUT_2") (pintype "output"))
    )
    (net (code "157") (name "Net-(D116-DOUT)") (class "Default")
      (node (ref "D116") (pin "2") (pinfunction "DOUT_2") (pintype "output"))
      (node (ref "D117") (pin "4") (pinfunction "DIN_4") (pintype "input"))
    )
    (net (code "158") (name "Net-(D117-DOUT)") (class "Default")
      (node (ref "D117") (pin "2") (pinfunction "DOUT_2") (pintype "output"))
      (node (ref "D118") (pin "4") (pinfunction "DIN_4") (pintype "input"))
    )
    (net (code "159") (name "Net-(D118-DOUT)") (class "Default")
      (node (ref "D118") (pin "2") (pinfunction "DOUT_2") (pintype "output"))
      (node (ref "D119") (pin "4") (pinfunction "DIN_4") (pintype "input"))
    )
    (net (code "160") (name "Net-(D119-DOUT)") (class "Default")
      (node (ref "D119") (pin "2") (pinfunction "DOUT_2") (pintype "output"))
      (node (ref "D120") (pin "4") (pinfunction "DIN_4") (pintype "input"))
    )
    (net (code "161") (name "Net-(D120-DOUT)") (class "Default")
      (node (ref "D120") (pin "2") (pinfunction "DOUT_2") (pintype "output"))
      (node (ref "D121") (pin "4") (pinfunction "DIN_4") (pintype "input"))
    )
    (net (code "162") (name "Net-(D121-DOUT)") (class "Default")
      (node (ref "D121") (pin "2") (pinfunction "DOUT_2") (pintype "output"))
      (node (ref "D122") (pin "4") (pinfunction "DIN_4") (pintype "input"))
    )
    (net (code "163") (name "Net-(D122-DOUT)") (class "Default")
      (node (ref "D122") (pin "2") (pinfunction "DOUT_2") (pintype "output"))
      (node (ref "D123") (pin "4") (pinfunction "DIN_4") (pintype "input"))
    )
    (net (code "164") (name "Net-(J1A-CC1)") (class "Default")
      (node (ref "J1") (pin "A5") (pinfunction "CC1_A5") (pintype "passive"))
      (node (ref "R2") (pin "1") (pinfunction "1_1") (pintype "passive"))
    )
    (net (code "165") (name "Net-(J1A-CC2)") (class "Default")
      (node (ref "J1") (pin "B5") (pinfunction "CC2_B5") (pintype "passive"))
      (node (ref "R4") (pin "1") (pinfunction "1_1") (pintype "passive"))
    )
    (net (code "166") (name "Net-(R3-Pad1)") (class "Default")
      (node (ref "R3") (pin "1") (pinfunction "1_1") (pintype "passive"))
      (node (ref "SW1") (pin "34") (pintype "passive"))
    )
    (net (code "167") (name "VBUS") (class "Default")
      (node (ref "C12") (pin "2") (pinfunction "2_2") (pintype "passive"))
      (node (ref "C17") (pin "2") (pinfunction "2_2") (pintype "passive"))
      (node (ref "C18") (pin "2") (pinfunction "2_2") (pintype "passive"))
      (node (ref "C19") (pin "2") (pinfunction "2_2") (pintype "passive"))
      (node (ref "C20") (pin "2") (pinfunction "2_2") (pintype "passive"))
      (node (ref "C21") (pin "2") (pinfunction "2_2") (pintype "passive"))
      (node (ref "C22") (pin "2") (pinfunction "2_2") (pintype "passive"))
      (node (ref "C23") (pin "2") (pinfunction "2_2") (pintype "passive"))
      (node (ref "C24") (pin "2") (pinfunction "2_2") (pintype "passive"))
      (node (ref "C25") (pin "2") (pinfunction "2_2") (pintype "passive"))
      (node (ref "C26") (pin "2") (pinfunction "2_2") (pintype "passive"))
      (node (ref "C27") (pin "2") (pinfunction "2_2") (pintype "passive"))
      (node (ref "C28") (pin "2") (pinfunction "2_2") (pintype "passive"))
      (node (ref "C29") (pin "2") (pinfunction "2_2") (pintype "passive"))
      (node (ref "C30") (pin "2") (pinfunction "2_2") (pintype "passive"))
      (node (ref "C31") (pin "2") (pinfunction "2_2") (pintype "passive"))
      (node (ref "C32") (pin "2") (pinfunction "2_2") (pintype "passive"))
      (node (ref "C33") (pin "2") (pinfunction "2_2") (pintype "passive"))
      (node (ref "C34") (pin "2") (pinfunction "2_2") (pintype "passive"))
      (node (ref "C35") (pin "2") (pinfunction "2_2") (pintype "passive"))
      (node (ref "C36") (pin "2") (pinfunction "2_2") (pintype "passive"))
      (node (ref "C37") (pin "2") (pinfunction "2_2") (pintype "passive"))
      (node (ref "C38") (pin "2") (pinfunction "2_2") (pintype "passive"))
      (node (ref "C39") (pin "2") (pinfunction "2_2") (pintype "passive"))
      (node (ref "C40") (pin "2") (pinfunction "2_2") (pintype "passive"))
      (node (ref "C41") (pin "2") (pinfunction "2_2") (pintype "passive"))
      (node (ref "C42") (pin "2") (pinfunction "2_2") (pintype "passive"))
      (node (ref "C43") (pin "2") (pinfunction "2_2") (pintype "passive"))
      (node (ref "C44") (pin "2") (pinfunction "2_2") (pintype "passive"))
      (node (ref "C45") (pin "2") (pinfunction "2_2") (pintype "passive"))
      (node (ref "C46") (pin "2") (pinfunction "2_2") (pintype "passive"))
      (node (ref "C47") (pin "2") (pinfunction "2_2") (pintype "passive"))
      (node (ref "C48") (pin "2") (pinfunction "2_2") (pintype "passive"))
      (node (ref "C49") (pin "2") (pinfunction "2_2") (pintype "passive"))
      (node (ref "C50") (pin "2") (pinfunction "2_2") (pintype "passive"))
      (node (ref "C51") (pin "2") (pinfunction "2_2") (pintype "passive"))
      (node (ref "C52") (pin "2") (pinfunction "2_2") (pintype "passive"))
      (node (ref "C53") (pin "2") (pinfunction "2_2") (pintype "passive"))
      (node (ref "C54") (pin "2") (pinfunction "2_2") (pintype "passive"))
      (node (ref "C55") (pin "2") (pinfunction "2_2") (pintype "passive"))
      (node (ref "C56") (pin "2") (pinfunction "2_2") (pintype "passive"))
      (node (ref "C57") (pin "2") (pinfunction "2_2") (pintype "passive"))
      (node (ref "C58") (pin "2") (pinfunction "2_2") (pintype "passive"))
      (node (ref "C59") (pin "2") (pinfunction "2_2") (pintype "passive"))
      (node (ref "C60") (pin "2") (pinfunction "2_2") (pintype "passive"))
      (node (ref "C61") (pin "2") (pinfunction "2_2") (pintype "passive"))
      (node (ref "C62") (pin "2") (pinfunction "2_2") (pintype "passive"))
      (node (ref "C63") (pin "2") (pinfunction "2_2") (pintype "passive"))
      (node (ref "C64") (pin "2") (pinfunction "2_2") (pintype "passive"))
      (node (ref "C65") (pin "2") (pinfunction "2_2") (pintype "passive"))
      (node (ref "C66") (pin "2") (pinfunction "2_2") (pintype "passive"))
      (node (ref "C67") (pin "2") (pinfunction "2_2") (pintype "passive"))
      (node (ref "C68") (pin "2") (pinfunction "2_2") (pintype "passive"))
      (node (ref "C69") (pin "2") (pinfunction "2_2") (pintype "passive"))
      (node (ref "C70") (pin "2") (pinfunction "2_2") (pintype "passive"))
      (node (ref "C71") (pin "2") (pinfunction "2_2") (pintype "passive"))
      (node (ref "C72") (pin "2") (pinfunction "2_2") (pintype "passive"))
      (node (ref "C73") (pin "2") (pinfunction "2_2") (pintype "passive"))
      (node (ref "C74") (pin "2") (pinfunction "2_2") (pintype "passive"))
      (node (ref "C75") (pin "2") (pinfunction "2_2") (pintype "passive"))
      (node (ref "C76") (pin "2") (pinfunction "2_2") (pintype "passive"))
      (node (ref "C77") (pin "2") (pinfunction "2_2") (pintype "passive"))
      (node (ref "D1") (pin "5") (pinfunction "VBUS_5") (pintype "power_in"))
      (node (ref "D100") (pin "1") (pinfunction "VDD_1") (pintype "power_in"))
      (node (ref "D101") (pin "1") (pinfunction "VDD_1") (pintype "power_in"))
      (node (ref "D102") (pin "1") (pinfunction "VDD_1") (pintype "power_in"))
      (node (ref "D103") (pin "1") (pinfunction "VDD_1") (pintype "power_in"))
      (node (ref "D104") (pin "3") (pinfunction "GND_3") (pintype "power_in"))
      (node (ref "D105") (pin "3") (pinfunction "GND_3") (pintype "power_in"))
      (node (ref "D106") (pin "3") (pinfunction "GND_3") (pintype "power_in"))
      (node (ref "D107") (pin "3") (pinfunction "GND_3") (pintype "power_in"))
      (node (ref "D108") (pin "3") (pinfunction "GND_3") (pintype "power_in"))
      (node (ref "D109") (pin "3") (pinfunction "GND_3") (pintype "power_in"))
      (node (ref "D110") (pin "3") (pinfunction "GND_3") (pintype "power_in"))
      (node (ref "D111") (pin "3") (pinfunction "GND_3") (pintype "power_in"))
      (node (ref "D112") (pin "3") (pinfunction "GND_3") (pintype "power_in"))
      (node (ref "D113") (pin "3") (pinfunction "GND_3") (pintype "power_in"))
      (node (ref "D114") (pin "3") (pinfunction "GND_3") (pintype "power_in"))
      (node (ref "D115") (pin "3") (pinfunction "GND_3") (pintype "power_in"))
      (node (ref "D116") (pin "1") (pinfunction "VDD_1") (pintype "power_in"))
      (node (ref "D117") (pin "1") (pinfunction "VDD_1") (pintype "power_in"))
      (node (ref "D118") (pin "1") (pinfunction "VDD_1") (pintype "power_in"))
      (node (ref "D119") (pin "1") (pinfunction "VDD_1") (pintype "power_in"))
      (node (ref "D120") (pin "1") (pinfunction "VDD_1") (pintype "power_in"))
      (node (ref "D121") (pin "1") (pinfunction "VDD_1") (pintype "power_in"))
      (node (ref "D122") (pin "1") (pinfunction "VDD_1") (pintype "power_in"))
      (node (ref "D123") (pin "1") (pinfunction "VDD_1") (pintype "power_in"))
      (node (ref "D63") (pin "1") (pinfunction "VDD_1") (pintype "power_in"))
      (node (ref "D64") (pin "1") (pinfunction "VDD_1") (pintype "power_in"))
      (node (ref "D65") (pin "1") (pinfunction "VDD_1") (pintype "power_in"))
      (node (ref "D66") (pin "1") (pinfunction "VDD_1") (pintype "power_in"))
      (node (ref "D67") (pin "1") (pinfunction "VDD_1") (pintype "power_in"))
      (node (ref "D68") (pin "1") (pinfunction "VDD_1") (pintype "power_in"))
      (node (ref "D69") (pin "1") (pinfunction "VDD_1") (pintype "power_in"))
      (node (ref "D70") (pin "1") (pinfunction "VDD_1") (pintype "power_in"))
      (node (ref "D71") (pin "1") (pinfunction "VDD_1") (pintype "power_in"))
      (node (ref "D72") (pin "1") (pinfunction "VDD_1") (pintype "power_in"))
      (node (ref "D73") (pin "1") (pinfunction "VDD_1") (pintype "power_in"))
      (node (ref "D74") (pin "1") (pinfunction "VDD_1") (pintype "power_in"))
      (node (ref "D75") (pin "1") (pinfunction "VDD_1") (pintype "power_in"))
      (node (ref "D76") (pin "1") (pinfunction "VDD_1") (pintype "power_in"))
      (node (ref "D77") (pin "3") (pinfunction "GND_3") (pintype "power_in"))
      (node (ref "D78") (pin "3") (pinfunction "GND_3") (pintype "power_in"))
      (node (ref "D79") (pin "3") (pinfunction "GND_3") (pintype "power_in"))
      (node (ref "D80") (pin "3") (pinfunction "GND_3") (pintype "power_in"))
      (node (ref "D81") (pin "3") (pinfunction "GND_3") (pintype "power_in"))
      (node (ref "D82") (pin "3") (pinfunction "GND_3") (pintype "power_in"))
      (node (ref "D83") (pin "3") (pinfunction "GND_3") (pintype "power_in"))
      (node (ref "D84") (pin "3") (pinfunction "GND_3") (pintype "power_in"))
      (node (ref "D85") (pin "3") (pinfunction "GND_3") (pintype "power_in"))
      (node (ref "D86") (pin "3") (pinfunction "GND_3") (pintype "power_in"))
      (node (ref "D87") (pin "3") (pinfunction "GND_3") (pintype "power_in"))
      (node (ref "D88") (pin "3") (pinfunction "GND_3") (pintype "power_in"))
      (node (ref "D89") (pin "3") (pinfunction "GND_3") (pintype "power_in"))
      (node (ref "D90") (pin "3") (pinfunction "GND_3") (pintype "power_in"))
      (node (ref "D91") (pin "1") (pinfunction "VDD_1") (pintype "power_in"))
      (node (ref "D92") (pin "1") (pinfunction "VDD_1") (pintype "power_in"))
      (node (ref "D93") (pin "1") (pinfunction "VDD_1") (pintype "power_in"))
      (node (ref "D94") (pin "1") (pinfunction "VDD_1") (pintype "power_in"))
      (node (ref "D95") (pin "1") (pinfunction "VDD_1") (pintype "power_in"))
      (node (ref "D96") (pin "1") (pinfunction "VDD_1") (pintype "power_in"))
      (node (ref "D97") (pin "1") (pinfunction "VDD_1") (pintype "power_in"))
      (node (ref "D98") (pin "1") (pinfunction "VDD_1") (pintype "power_in"))
      (node (ref "D99") (pin "1") (pinfunction "VDD_1") (pintype "power_in"))
      (node (ref "J1") (pin "A4-B9") (pinfunction "VBUS_A4-B9") (pintype "power_in"))
      (node (ref "J1") (pin "B4-A9") (pinfunction "VBUS_B4-A9") (pintype "power_in"))
      (node (ref "U1") (pin "3") (pinfunction "Input_3") (pintype "power_in"))
    )
    (net (code "168") (name "unconnected-(D123-DOUT-Pad2)") (class "Default")
      (node (ref "D123") (pin "2") (pinfunction "DOUT_2") (pintype "output+no_connect"))
    )
    (net (code "169") (name "unconnected-(J1A-SBU1-PadA8)") (class "Default")
      (node (ref "J1") (pin "A8") (pinfunction "SBU1_A8") (pintype "passive+no_connect"))
    )
    (net (code "170") (name "unconnected-(J1A-SBU2-PadB8)") (class "Default")
      (node (ref "J1") (pin "B8") (pinfunction "SBU2_B8") (pintype "passive+no_connect"))
    )
    (net (code "171") (name "unconnected-(P1-PadMP1)") (class "Default")
      (node (ref "P1") (pin "MP1") (pinfunction "MP1_MP1") (pintype "passive+no_connect"))
    )
    (net (code "172") (name "unconnected-(P1-PadMP2)") (class "Default")
      (node (ref "P1") (pin "MP2") (pinfunction "MP2_MP2") (pintype "passive+no_connect"))
    )
    (net (code "173") (name "unconnected-(P2-PadMP1)") (class "Default")
      (node (ref "P2") (pin "MP1") (pinfunction "MP1_MP1") (pintype "passive+no_connect"))
    )
    (net (code "174") (name "unconnected-(P2-PadMP2)") (class "Default")
      (node (ref "P2") (pin "MP2") (pinfunction "MP2_MP2") (pintype "passive+no_connect"))
    )
    (net (code "175") (name "unconnected-(U2-GPIO0-Pad2)") (class "Default")
      (node (ref "U2") (pin "2") (pinfunction "GPIO0_2") (pintype "bidirectional+no_connect"))
    )
    (net (code "176") (name "unconnected-(U2-GPIO7-Pad9)") (class "Default")
      (node (ref "U2") (pin "9") (pinfunction "GPIO7_9") (pintype "bidirectional+no_connect"))
    )
    (net (code "177") (name "unconnected-(U2-GPIO8-Pad11)") (class "Default")
      (node (ref "U2") (pin "11") (pinfunction "GPIO8_11") (pintype "bidirectional+no_connect"))
    )
    (net (code "178") (name "unconnected-(U2-GPIO14-Pad17)") (class "Default")
      (node (ref "U2") (pin "17") (pinfunction "GPIO14_17") (pintype "bidirectional+no_connect"))
    )
    (net (code "179") (name "unconnected-(U2-GPIO15-Pad18)") (class "Default")
      (node (ref "U2") (pin "18") (pinfunction "GPIO15_18") (pintype "bidirectional+no_connect"))
    )
    (net (code "180") (name "unconnected-(U2-GPIO22-Pad34)") (class "Default")
      (node (ref "U2") (pin "34") (pinfunction "GPIO22_34") (pintype "bidirectional+no_connect"))
    )
    (net (code "181") (name "unconnected-(U2-GPIO27_ADC1-Pad39)") (class "Default")
      (node (ref "U2") (pin "39") (pinfunction "GPIO27_ADC1_39") (pintype "bidirectional+no_connect"))
    )
    (net (code "182") (name "unconnected-(U2-GPIO28_ADC2-Pad40)") (class "Default")
      (node (ref "U2") (pin "40") (pinfunction "GPIO28_ADC2_40") (pintype "bidirectional+no_connect"))
    )
    (net (code "183") (name "unconnected-(U2-RUN-Pad26)") (class "Default")
      (node (ref "U2") (pin "26") (pinfunction "RUN_26") (pintype "input+no_connect"))
    )
  )
)
